# sketchv21111_0.net
KiCad netlist of a schematic drawn in EAGLE
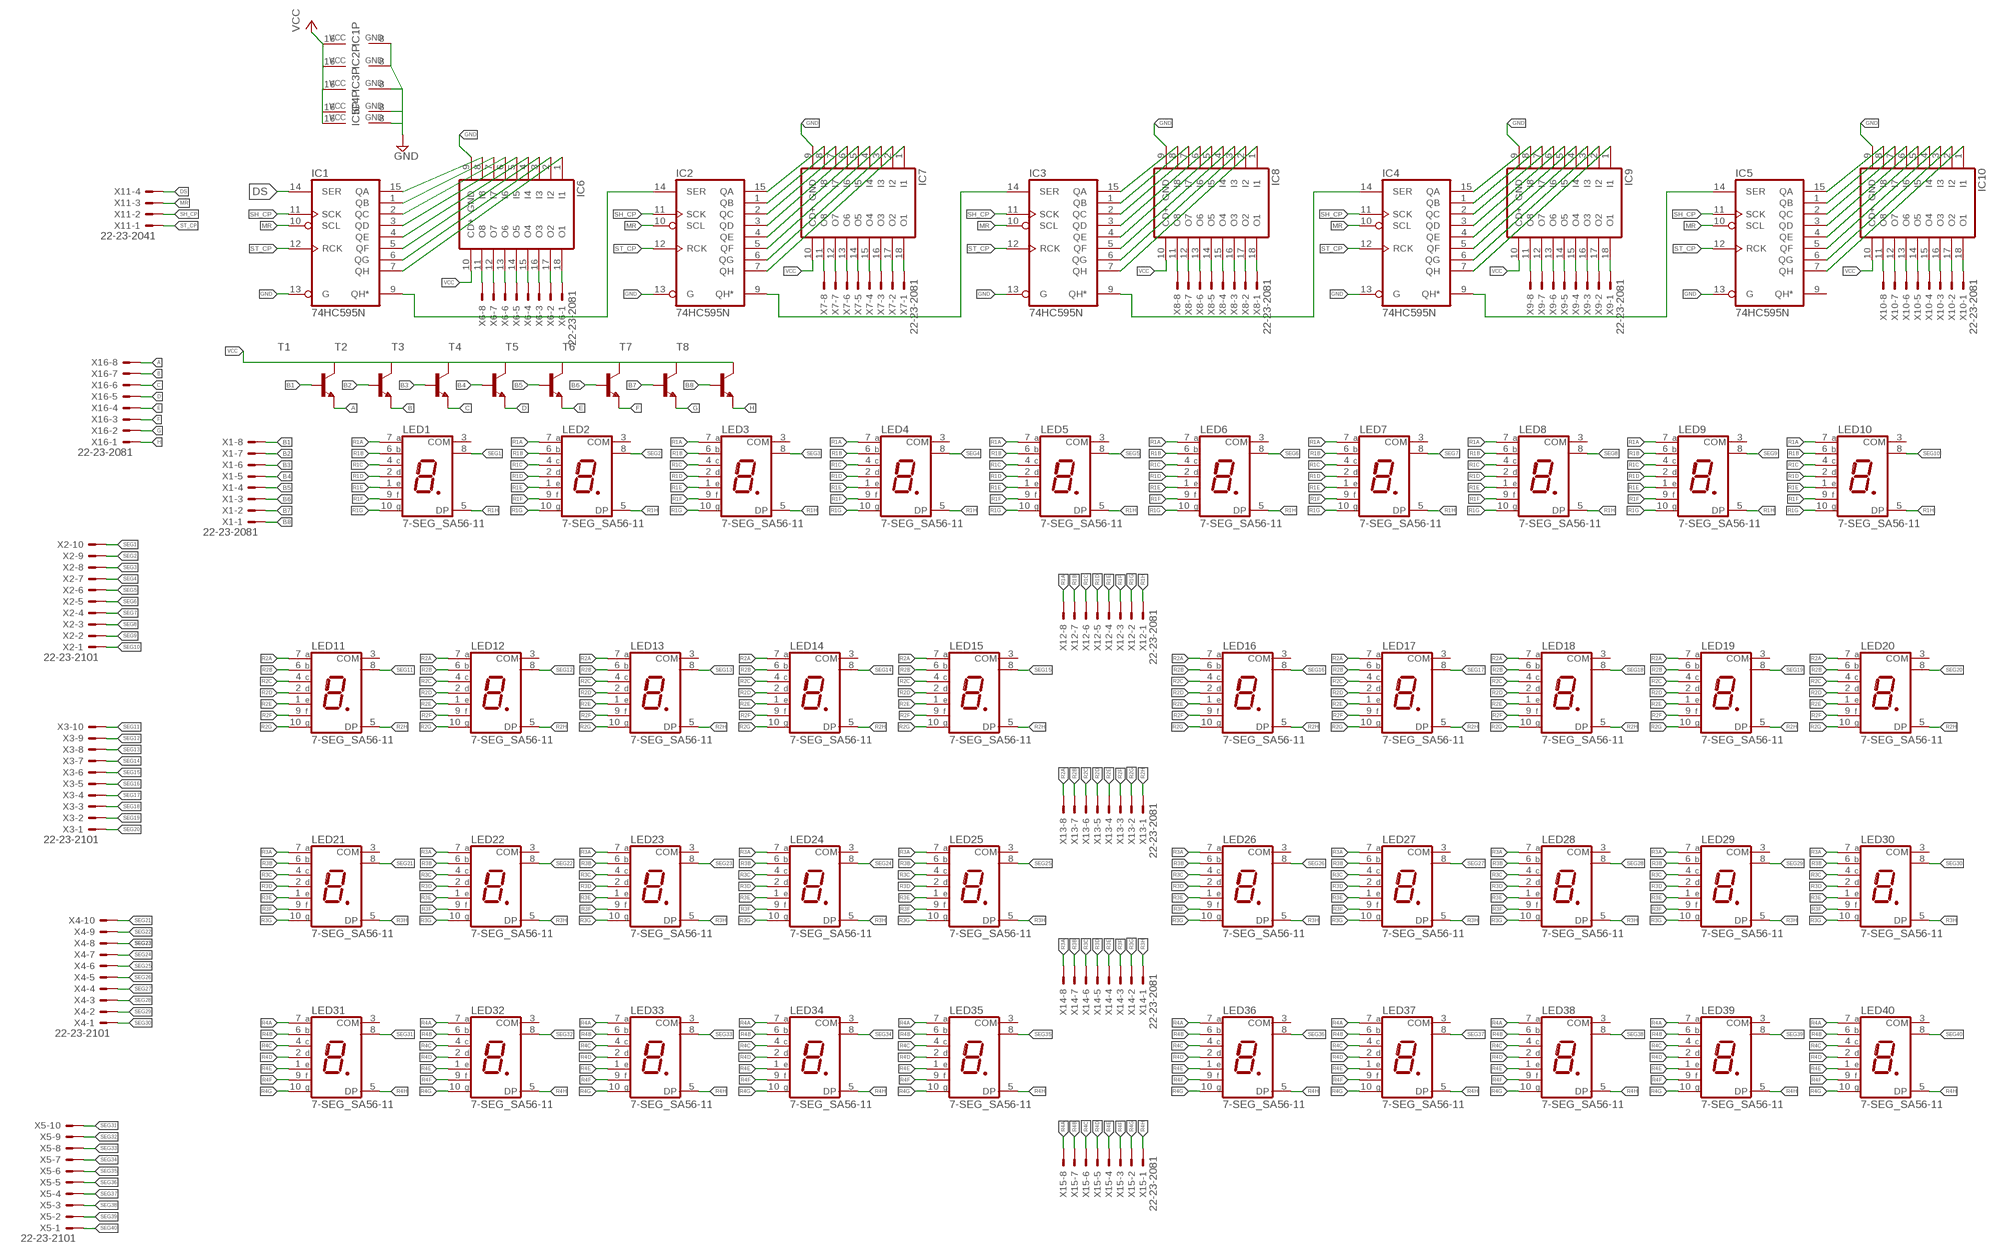
[diagram p0: schematic, sheet 1]

(export (version "E")
  (design (tool "Eeschema 10.0.6"))
  (components
    (comp (ref "IC1")
      (value "74HC595N")
      (footprint "eagle-import:DIL16")
      (libsource (lib "eagle-import") (part "74595NHC"))
    )
    (comp (ref "IC2")
      (value "74HC595N")
      (footprint "eagle-import:DIL16")
      (libsource (lib "eagle-import") (part "74595NHC"))
    )
    (comp (ref "IC3")
      (value "74HC595N")
      (footprint "eagle-import:DIL16")
      (libsource (lib "eagle-import") (part "74595NHC"))
    )
    (comp (ref "IC4")
      (value "74HC595N")
      (footprint "eagle-import:DIL16")
      (libsource (lib "eagle-import") (part "74595NHC"))
    )
    (comp (ref "IC5")
      (value "74HC595N")
      (footprint "eagle-import:DIL16")
      (libsource (lib "eagle-import") (part "74595NHC"))
    )
    (comp (ref "IC6")
      (value "ULN2803A")
      (footprint "eagle-import:DIL18")
      (libsource (lib "eagle-import") (part "ULN2803A"))
    )
    (comp (ref "IC7")
      (value "ULN2803A")
      (footprint "eagle-import:DIL18")
      (libsource (lib "eagle-import") (part "ULN2803A"))
    )
    (comp (ref "IC8")
      (value "ULN2803A")
      (footprint "eagle-import:DIL18")
      (libsource (lib "eagle-import") (part "ULN2803A"))
    )
    (comp (ref "IC9")
      (value "ULN2803A")
      (footprint "eagle-import:DIL18")
      (libsource (lib "eagle-import") (part "ULN2803A"))
    )
    (comp (ref "IC10")
      (value "ULN2803A")
      (footprint "eagle-import:DIL18")
      (libsource (lib "eagle-import") (part "ULN2803A"))
    )
    (comp (ref "LED1")
      (value "7-SEG_SA56-11")
      (footprint "eagle-import:SA56-11")
      (libsource (lib "eagle-import") (part "7-SEG_SA56-11"))
    )
    (comp (ref "LED2")
      (value "7-SEG_SA56-11")
      (footprint "eagle-import:SA56-11")
      (libsource (lib "eagle-import") (part "7-SEG_SA56-11"))
    )
    (comp (ref "LED3")
      (value "7-SEG_SA56-11")
      (footprint "eagle-import:SA56-11")
      (libsource (lib "eagle-import") (part "7-SEG_SA56-11"))
    )
    (comp (ref "LED4")
      (value "7-SEG_SA56-11")
      (footprint "eagle-import:SA56-11")
      (libsource (lib "eagle-import") (part "7-SEG_SA56-11"))
    )
    (comp (ref "LED5")
      (value "7-SEG_SA56-11")
      (footprint "eagle-import:SA56-11")
      (libsource (lib "eagle-import") (part "7-SEG_SA56-11"))
    )
    (comp (ref "LED6")
      (value "7-SEG_SA56-11")
      (footprint "eagle-import:SA56-11")
      (libsource (lib "eagle-import") (part "7-SEG_SA56-11"))
    )
    (comp (ref "LED7")
      (value "7-SEG_SA56-11")
      (footprint "eagle-import:SA56-11")
      (libsource (lib "eagle-import") (part "7-SEG_SA56-11"))
    )
    (comp (ref "LED8")
      (value "7-SEG_SA56-11")
      (footprint "eagle-import:SA56-11")
      (libsource (lib "eagle-import") (part "7-SEG_SA56-11"))
    )
    (comp (ref "LED9")
      (value "7-SEG_SA56-11")
      (footprint "eagle-import:SA56-11")
      (libsource (lib "eagle-import") (part "7-SEG_SA56-11"))
    )
    (comp (ref "LED10")
      (value "7-SEG_SA56-11")
      (footprint "eagle-import:SA56-11")
      (libsource (lib "eagle-import") (part "7-SEG_SA56-11"))
    )
    (comp (ref "LED11")
      (value "7-SEG_SA56-11")
      (footprint "eagle-import:SA56-11")
      (libsource (lib "eagle-import") (part "7-SEG_SA56-11"))
    )
    (comp (ref "LED12")
      (value "7-SEG_SA56-11")
      (footprint "eagle-import:SA56-11")
      (libsource (lib "eagle-import") (part "7-SEG_SA56-11"))
    )
    (comp (ref "LED13")
      (value "7-SEG_SA56-11")
      (footprint "eagle-import:SA56-11")
      (libsource (lib "eagle-import") (part "7-SEG_SA56-11"))
    )
    (comp (ref "LED14")
      (value "7-SEG_SA56-11")
      (footprint "eagle-import:SA56-11")
      (libsource (lib "eagle-import") (part "7-SEG_SA56-11"))
    )
    (comp (ref "LED15")
      (value "7-SEG_SA56-11")
      (footprint "eagle-import:SA56-11")
      (libsource (lib "eagle-import") (part "7-SEG_SA56-11"))
    )
    (comp (ref "LED16")
      (value "7-SEG_SA56-11")
      (footprint "eagle-import:SA56-11")
      (libsource (lib "eagle-import") (part "7-SEG_SA56-11"))
    )
    (comp (ref "LED17")
      (value "7-SEG_SA56-11")
      (footprint "eagle-import:SA56-11")
      (libsource (lib "eagle-import") (part "7-SEG_SA56-11"))
    )
    (comp (ref "LED18")
      (value "7-SEG_SA56-11")
      (footprint "eagle-import:SA56-11")
      (libsource (lib "eagle-import") (part "7-SEG_SA56-11"))
    )
    (comp (ref "LED19")
      (value "7-SEG_SA56-11")
      (footprint "eagle-import:SA56-11")
      (libsource (lib "eagle-import") (part "7-SEG_SA56-11"))
    )
    (comp (ref "LED20")
      (value "7-SEG_SA56-11")
      (footprint "eagle-import:SA56-11")
      (libsource (lib "eagle-import") (part "7-SEG_SA56-11"))
    )
    (comp (ref "LED21")
      (value "7-SEG_SA56-11")
      (footprint "eagle-import:SA56-11")
      (libsource (lib "eagle-import") (part "7-SEG_SA56-11"))
    )
    (comp (ref "LED22")
      (value "7-SEG_SA56-11")
      (footprint "eagle-import:SA56-11")
      (libsource (lib "eagle-import") (part "7-SEG_SA56-11"))
    )
    (comp (ref "LED23")
      (value "7-SEG_SA56-11")
      (footprint "eagle-import:SA56-11")
      (libsource (lib "eagle-import") (part "7-SEG_SA56-11"))
    )
    (comp (ref "LED24")
      (value "7-SEG_SA56-11")
      (footprint "eagle-import:SA56-11")
      (libsource (lib "eagle-import") (part "7-SEG_SA56-11"))
    )
    (comp (ref "LED25")
      (value "7-SEG_SA56-11")
      (footprint "eagle-import:SA56-11")
      (libsource (lib "eagle-import") (part "7-SEG_SA56-11"))
    )
    (comp (ref "LED26")
      (value "7-SEG_SA56-11")
      (footprint "eagle-import:SA56-11")
      (libsource (lib "eagle-import") (part "7-SEG_SA56-11"))
    )
    (comp (ref "LED27")
      (value "7-SEG_SA56-11")
      (footprint "eagle-import:SA56-11")
      (libsource (lib "eagle-import") (part "7-SEG_SA56-11"))
    )
    (comp (ref "LED28")
      (value "7-SEG_SA56-11")
      (footprint "eagle-import:SA56-11")
      (libsource (lib "eagle-import") (part "7-SEG_SA56-11"))
    )
    (comp (ref "LED29")
      (value "7-SEG_SA56-11")
      (footprint "eagle-import:SA56-11")
      (libsource (lib "eagle-import") (part "7-SEG_SA56-11"))
    )
    (comp (ref "LED30")
      (value "7-SEG_SA56-11")
      (footprint "eagle-import:SA56-11")
      (libsource (lib "eagle-import") (part "7-SEG_SA56-11"))
    )
    (comp (ref "LED31")
      (value "7-SEG_SA56-11")
      (footprint "eagle-import:SA56-11")
      (libsource (lib "eagle-import") (part "7-SEG_SA56-11"))
    )
    (comp (ref "LED32")
      (value "7-SEG_SA56-11")
      (footprint "eagle-import:SA56-11")
      (libsource (lib "eagle-import") (part "7-SEG_SA56-11"))
    )
    (comp (ref "LED33")
      (value "7-SEG_SA56-11")
      (footprint "eagle-import:SA56-11")
      (libsource (lib "eagle-import") (part "7-SEG_SA56-11"))
    )
    (comp (ref "LED34")
      (value "7-SEG_SA56-11")
      (footprint "eagle-import:SA56-11")
      (libsource (lib "eagle-import") (part "7-SEG_SA56-11"))
    )
    (comp (ref "LED35")
      (value "7-SEG_SA56-11")
      (footprint "eagle-import:SA56-11")
      (libsource (lib "eagle-import") (part "7-SEG_SA56-11"))
    )
    (comp (ref "LED36")
      (value "7-SEG_SA56-11")
      (footprint "eagle-import:SA56-11")
      (libsource (lib "eagle-import") (part "7-SEG_SA56-11"))
    )
    (comp (ref "LED37")
      (value "7-SEG_SA56-11")
      (footprint "eagle-import:SA56-11")
      (libsource (lib "eagle-import") (part "7-SEG_SA56-11"))
    )
    (comp (ref "LED38")
      (value "7-SEG_SA56-11")
      (footprint "eagle-import:SA56-11")
      (libsource (lib "eagle-import") (part "7-SEG_SA56-11"))
    )
    (comp (ref "LED39")
      (value "7-SEG_SA56-11")
      (footprint "eagle-import:SA56-11")
      (libsource (lib "eagle-import") (part "7-SEG_SA56-11"))
    )
    (comp (ref "LED40")
      (value "7-SEG_SA56-11")
      (footprint "eagle-import:SA56-11")
      (libsource (lib "eagle-import") (part "7-SEG_SA56-11"))
    )
    (comp (ref "T1")
      (value "-NPN-TO92")
      (footprint "eagle-import:TO92")
      (libsource (lib "eagle-import") (part "-NPN-TO92"))
    )
    (comp (ref "T2")
      (value "-NPN-TO92")
      (footprint "eagle-import:TO92")
      (libsource (lib "eagle-import") (part "-NPN-TO92"))
    )
    (comp (ref "T3")
      (value "-NPN-TO92")
      (footprint "eagle-import:TO92")
      (libsource (lib "eagle-import") (part "-NPN-TO92"))
    )
    (comp (ref "T4")
      (value "-NPN-TO92")
      (footprint "eagle-import:TO92")
      (libsource (lib "eagle-import") (part "-NPN-TO92"))
    )
    (comp (ref "T5")
      (value "-NPN-TO92")
      (footprint "eagle-import:TO92")
      (libsource (lib "eagle-import") (part "-NPN-TO92"))
    )
    (comp (ref "T6")
      (value "-NPN-TO92")
      (footprint "eagle-import:TO92")
      (libsource (lib "eagle-import") (part "-NPN-TO92"))
    )
    (comp (ref "T7")
      (value "-NPN-TO92")
      (footprint "eagle-import:TO92")
      (libsource (lib "eagle-import") (part "-NPN-TO92"))
    )
    (comp (ref "T8")
      (value "-NPN-TO92")
      (footprint "eagle-import:TO92")
      (libsource (lib "eagle-import") (part "-NPN-TO92"))
    )
    (comp (ref "X1")
      (value "22-23-2081")
      (footprint "eagle-import:22-23-2081")
      (fields (field (name "MF") "MOLEX"))
      (libsource (lib "eagle-import") (part "22-23-2081"))
    )
    (comp (ref "X2")
      (value "22-23-2101")
      (footprint "eagle-import:22-23-2101")
      (fields (field (name "MF") "MOLEX"))
      (libsource (lib "eagle-import") (part "22-23-2101"))
    )
    (comp (ref "X3")
      (value "22-23-2101")
      (footprint "eagle-import:22-23-2101")
      (fields (field (name "MF") "MOLEX"))
      (libsource (lib "eagle-import") (part "22-23-2101"))
    )
    (comp (ref "X4")
      (value "22-23-2101")
      (footprint "eagle-import:22-23-2101")
      (fields (field (name "MF") "MOLEX"))
      (libsource (lib "eagle-import") (part "22-23-2101"))
    )
    (comp (ref "X5")
      (value "22-23-2101")
      (footprint "eagle-import:22-23-2101")
      (fields (field (name "MF") "MOLEX"))
      (libsource (lib "eagle-import") (part "22-23-2101"))
    )
    (comp (ref "X6")
      (value "22-23-2081")
      (footprint "eagle-import:22-23-2081")
      (fields (field (name "MF") "MOLEX"))
      (libsource (lib "eagle-import") (part "22-23-2081"))
    )
    (comp (ref "X7")
      (value "22-23-2081")
      (footprint "eagle-import:22-23-2081")
      (fields (field (name "MF") "MOLEX"))
      (libsource (lib "eagle-import") (part "22-23-2081"))
    )
    (comp (ref "X8")
      (value "22-23-2081")
      (footprint "eagle-import:22-23-2081")
      (fields (field (name "MF") "MOLEX"))
      (libsource (lib "eagle-import") (part "22-23-2081"))
    )
    (comp (ref "X9")
      (value "22-23-2081")
      (footprint "eagle-import:22-23-2081")
      (fields (field (name "MF") "MOLEX"))
      (libsource (lib "eagle-import") (part "22-23-2081"))
    )
    (comp (ref "X10")
      (value "22-23-2081")
      (footprint "eagle-import:22-23-2081")
      (fields (field (name "MF") "MOLEX"))
      (libsource (lib "eagle-import") (part "22-23-2081"))
    )
    (comp (ref "X11")
      (value "22-23-2041")
      (footprint "eagle-import:22-23-2041")
      (fields (field (name "MF") "MOLEX"))
      (libsource (lib "eagle-import") (part "22-23-2041"))
    )
    (comp (ref "X12")
      (value "22-23-2081")
      (footprint "eagle-import:22-23-2081")
      (fields (field (name "MF") "MOLEX"))
      (libsource (lib "eagle-import") (part "22-23-2081"))
    )
    (comp (ref "X13")
      (value "22-23-2081")
      (footprint "eagle-import:22-23-2081")
      (fields (field (name "MF") "MOLEX"))
      (libsource (lib "eagle-import") (part "22-23-2081"))
    )
    (comp (ref "X14")
      (value "22-23-2081")
      (footprint "eagle-import:22-23-2081")
      (fields (field (name "MF") "MOLEX"))
      (libsource (lib "eagle-import") (part "22-23-2081"))
    )
    (comp (ref "X15")
      (value "22-23-2081")
      (footprint "eagle-import:22-23-2081")
      (fields (field (name "MF") "MOLEX"))
      (libsource (lib "eagle-import") (part "22-23-2081"))
    )
    (comp (ref "X16")
      (value "22-23-2081")
      (footprint "eagle-import:22-23-2081")
      (fields (field (name "MF") "MOLEX"))
      (libsource (lib "eagle-import") (part "22-23-2081"))
    )
  )
  (nets
    (net (code "1") (name "A") (class "Default")
      (node (ref "T1") (pin "1") (pinfunction "E_1") (pintype "passive"))
      (node (ref "X16") (pin "8") (pinfunction "S_8") (pintype "passive"))
    )
    (net (code "2") (name "B") (class "Default")
      (node (ref "T2") (pin "1") (pinfunction "E_1") (pintype "passive"))
      (node (ref "X16") (pin "7") (pinfunction "S_7") (pintype "passive"))
    )
    (net (code "3") (name "B1") (class "Default")
      (node (ref "T1") (pin "2") (pinfunction "B_2") (pintype "passive"))
      (node (ref "X1") (pin "8") (pinfunction "S_8") (pintype "passive"))
    )
    (net (code "4") (name "B2") (class "Default")
      (node (ref "T2") (pin "2") (pinfunction "B_2") (pintype "passive"))
      (node (ref "X1") (pin "7") (pinfunction "S_7") (pintype "passive"))
    )
    (net (code "5") (name "B3") (class "Default")
      (node (ref "T3") (pin "2") (pinfunction "B_2") (pintype "passive"))
      (node (ref "X1") (pin "6") (pinfunction "S_6") (pintype "passive"))
    )
    (net (code "6") (name "B4") (class "Default")
      (node (ref "T4") (pin "2") (pinfunction "B_2") (pintype "passive"))
      (node (ref "X1") (pin "5") (pinfunction "S_5") (pintype "passive"))
    )
    (net (code "7") (name "B5") (class "Default")
      (node (ref "T5") (pin "2") (pinfunction "B_2") (pintype "passive"))
      (node (ref "X1") (pin "4") (pinfunction "S_4") (pintype "passive"))
    )
    (net (code "8") (name "B6") (class "Default")
      (node (ref "T6") (pin "2") (pinfunction "B_2") (pintype "passive"))
      (node (ref "X1") (pin "3") (pinfunction "S_3") (pintype "passive"))
    )
    (net (code "9") (name "B7") (class "Default")
      (node (ref "T7") (pin "2") (pinfunction "B_2") (pintype "passive"))
      (node (ref "X1") (pin "2") (pinfunction "S_2") (pintype "passive"))
    )
    (net (code "10") (name "B8") (class "Default")
      (node (ref "T8") (pin "2") (pinfunction "B_2") (pintype "passive"))
      (node (ref "X1") (pin "1") (pinfunction "S_1") (pintype "passive"))
    )
    (net (code "11") (name "C") (class "Default")
      (node (ref "T3") (pin "1") (pinfunction "E_1") (pintype "passive"))
      (node (ref "X16") (pin "6") (pinfunction "S_6") (pintype "passive"))
    )
    (net (code "12") (name "D") (class "Default")
      (node (ref "T4") (pin "1") (pinfunction "E_1") (pintype "passive"))
      (node (ref "X16") (pin "5") (pinfunction "S_5") (pintype "passive"))
    )
    (net (code "13") (name "DS") (class "Default")
      (node (ref "IC1") (pin "14") (pinfunction "SER_14") (pintype "input"))
      (node (ref "X11") (pin "4") (pinfunction "S_4") (pintype "passive"))
    )
    (net (code "14") (name "E") (class "Default")
      (node (ref "T5") (pin "1") (pinfunction "E_1") (pintype "passive"))
      (node (ref "X16") (pin "4") (pinfunction "S_4") (pintype "passive"))
    )
    (net (code "15") (name "F") (class "Default")
      (node (ref "T6") (pin "1") (pinfunction "E_1") (pintype "passive"))
      (node (ref "X16") (pin "3") (pinfunction "S_3") (pintype "passive"))
    )
    (net (code "16") (name "G") (class "Default")
      (node (ref "T7") (pin "1") (pinfunction "E_1") (pintype "passive"))
      (node (ref "X16") (pin "2") (pinfunction "S_2") (pintype "passive"))
    )
    (net (code "17") (name "GND") (class "Default")
      (node (ref "IC1") (pin "13") (pinfunction "G_13") (pintype "input"))
      (node (ref "IC1") (pin "8") (pinfunction "GND_8") (pintype "power_in"))
      (node (ref "IC10") (pin "9") (pinfunction "GND_9") (pintype "power_in"))
      (node (ref "IC2") (pin "13") (pinfunction "G_13") (pintype "input"))
      (node (ref "IC2") (pin "8") (pinfunction "GND_8") (pintype "power_in"))
      (node (ref "IC3") (pin "13") (pinfunction "G_13") (pintype "input"))
      (node (ref "IC3") (pin "8") (pinfunction "GND_8") (pintype "power_in"))
      (node (ref "IC4") (pin "13") (pinfunction "G_13") (pintype "input"))
      (node (ref "IC4") (pin "8") (pinfunction "GND_8") (pintype "power_in"))
      (node (ref "IC5") (pin "13") (pinfunction "G_13") (pintype "input"))
      (node (ref "IC5") (pin "8") (pinfunction "GND_8") (pintype "power_in"))
      (node (ref "IC6") (pin "9") (pinfunction "GND_9") (pintype "power_in"))
      (node (ref "IC7") (pin "9") (pinfunction "GND_9") (pintype "power_in"))
      (node (ref "IC8") (pin "9") (pinfunction "GND_9") (pintype "power_in"))
      (node (ref "IC9") (pin "9") (pinfunction "GND_9") (pintype "power_in"))
    )
    (net (code "18") (name "H") (class "Default")
      (node (ref "T8") (pin "1") (pinfunction "E_1") (pintype "passive"))
      (node (ref "X16") (pin "1") (pinfunction "S_1") (pintype "passive"))
    )
    (net (code "19") (name "MR") (class "Default")
      (node (ref "IC1") (pin "10") (pinfunction "SCL_10") (pintype "input"))
      (node (ref "IC2") (pin "10") (pinfunction "SCL_10") (pintype "input"))
      (node (ref "IC3") (pin "10") (pinfunction "SCL_10") (pintype "input"))
      (node (ref "IC4") (pin "10") (pinfunction "SCL_10") (pintype "input"))
      (node (ref "IC5") (pin "10") (pinfunction "SCL_10") (pintype "input"))
      (node (ref "X11") (pin "3") (pinfunction "S_3") (pintype "passive"))
    )
    (net (code "20") (name "Net-(IC1A-QA)") (class "Default")
      (node (ref "IC1") (pin "15") (pinfunction "QA_15") (pintype "tri_state"))
      (node (ref "IC6") (pin "8") (pinfunction "I8_8") (pintype "input"))
    )
    (net (code "21") (name "Net-(IC1A-QB)") (class "Default")
      (node (ref "IC1") (pin "1") (pinfunction "QB_1") (pintype "tri_state"))
      (node (ref "IC6") (pin "7") (pinfunction "I7_7") (pintype "input"))
    )
    (net (code "22") (name "Net-(IC1A-QC)") (class "Default")
      (node (ref "IC1") (pin "2") (pinfunction "QC_2") (pintype "tri_state"))
      (node (ref "IC6") (pin "6") (pinfunction "I6_6") (pintype "input"))
    )
    (net (code "23") (name "Net-(IC1A-QD)") (class "Default")
      (node (ref "IC1") (pin "3") (pinfunction "QD_3") (pintype "tri_state"))
      (node (ref "IC6") (pin "5") (pinfunction "I5_5") (pintype "input"))
    )
    (net (code "24") (name "Net-(IC1A-QE)") (class "Default")
      (node (ref "IC1") (pin "4") (pinfunction "QE_4") (pintype "tri_state"))
      (node (ref "IC6") (pin "4") (pinfunction "I4_4") (pintype "input"))
    )
    (net (code "25") (name "Net-(IC1A-QF)") (class "Default")
      (node (ref "IC1") (pin "5") (pinfunction "QF_5") (pintype "tri_state"))
      (node (ref "IC6") (pin "3") (pinfunction "I3_3") (pintype "input"))
    )
    (net (code "26") (name "Net-(IC1A-QG)") (class "Default")
      (node (ref "IC1") (pin "6") (pinfunction "QG_6") (pintype "tri_state"))
      (node (ref "IC6") (pin "2") (pinfunction "I2_2") (pintype "input"))
    )
    (net (code "27") (name "Net-(IC1A-QH)") (class "Default")
      (node (ref "IC1") (pin "7") (pinfunction "QH_7") (pintype "tri_state"))
      (node (ref "IC6") (pin "1") (pinfunction "I1_1") (pintype "input"))
    )
    (net (code "28") (name "Net-(IC1A-QH*)") (class "Default")
      (node (ref "IC1") (pin "9") (pinfunction "QH*_9") (pintype "tri_state"))
      (node (ref "IC2") (pin "14") (pinfunction "SER_14") (pintype "input"))
    )
    (net (code "29") (name "Net-(IC2A-QA)") (class "Default")
      (node (ref "IC2") (pin "15") (pinfunction "QA_15") (pintype "tri_state"))
      (node (ref "IC7") (pin "8") (pinfunction "I8_8") (pintype "input"))
    )
    (net (code "30") (name "Net-(IC2A-QB)") (class "Default")
      (node (ref "IC2") (pin "1") (pinfunction "QB_1") (pintype "tri_state"))
      (node (ref "IC7") (pin "7") (pinfunction "I7_7") (pintype "input"))
    )
    (net (code "31") (name "Net-(IC2A-QC)") (class "Default")
      (node (ref "IC2") (pin "2") (pinfunction "QC_2") (pintype "tri_state"))
      (node (ref "IC7") (pin "6") (pinfunction "I6_6") (pintype "input"))
    )
    (net (code "32") (name "Net-(IC2A-QD)") (class "Default")
      (node (ref "IC2") (pin "3") (pinfunction "QD_3") (pintype "tri_state"))
      (node (ref "IC7") (pin "5") (pinfunction "I5_5") (pintype "input"))
    )
    (net (code "33") (name "Net-(IC2A-QE)") (class "Default")
      (node (ref "IC2") (pin "4") (pinfunction "QE_4") (pintype "tri_state"))
      (node (ref "IC7") (pin "4") (pinfunction "I4_4") (pintype "input"))
    )
    (net (code "34") (name "Net-(IC2A-QF)") (class "Default")
      (node (ref "IC2") (pin "5") (pinfunction "QF_5") (pintype "tri_state"))
      (node (ref "IC7") (pin "3") (pinfunction "I3_3") (pintype "input"))
    )
    (net (code "35") (name "Net-(IC2A-QG)") (class "Default")
      (node (ref "IC2") (pin "6") (pinfunction "QG_6") (pintype "tri_state"))
      (node (ref "IC7") (pin "2") (pinfunction "I2_2") (pintype "input"))
    )
    (net (code "36") (name "Net-(IC2A-QH)") (class "Default")
      (node (ref "IC2") (pin "7") (pinfunction "QH_7") (pintype "tri_state"))
      (node (ref "IC7") (pin "1") (pinfunction "I1_1") (pintype "input"))
    )
    (net (code "37") (name "Net-(IC2A-QH*)") (class "Default")
      (node (ref "IC2") (pin "9") (pinfunction "QH*_9") (pintype "tri_state"))
      (node (ref "IC3") (pin "14") (pinfunction "SER_14") (pintype "input"))
    )
    (net (code "38") (name "Net-(IC3A-QA)") (class "Default")
      (node (ref "IC3") (pin "15") (pinfunction "QA_15") (pintype "tri_state"))
      (node (ref "IC8") (pin "8") (pinfunction "I8_8") (pintype "input"))
    )
    (net (code "39") (name "Net-(IC3A-QB)") (class "Default")
      (node (ref "IC3") (pin "1") (pinfunction "QB_1") (pintype "tri_state"))
      (node (ref "IC8") (pin "7") (pinfunction "I7_7") (pintype "input"))
    )
    (net (code "40") (name "Net-(IC3A-QC)") (class "Default")
      (node (ref "IC3") (pin "2") (pinfunction "QC_2") (pintype "tri_state"))
      (node (ref "IC8") (pin "6") (pinfunction "I6_6") (pintype "input"))
    )
    (net (code "41") (name "Net-(IC3A-QD)") (class "Default")
      (node (ref "IC3") (pin "3") (pinfunction "QD_3") (pintype "tri_state"))
      (node (ref "IC8") (pin "5") (pinfunction "I5_5") (pintype "input"))
    )
    (net (code "42") (name "Net-(IC3A-QE)") (class "Default")
      (node (ref "IC3") (pin "4") (pinfunction "QE_4") (pintype "tri_state"))
      (node (ref "IC8") (pin "4") (pinfunction "I4_4") (pintype "input"))
    )
    (net (code "43") (name "Net-(IC3A-QF)") (class "Default")
      (node (ref "IC3") (pin "5") (pinfunction "QF_5") (pintype "tri_state"))
      (node (ref "IC8") (pin "3") (pinfunction "I3_3") (pintype "input"))
    )
    (net (code "44") (name "Net-(IC3A-QG)") (class "Default")
      (node (ref "IC3") (pin "6") (pinfunction "QG_6") (pintype "tri_state"))
      (node (ref "IC8") (pin "2") (pinfunction "I2_2") (pintype "input"))
    )
    (net (code "45") (name "Net-(IC3A-QH)") (class "Default")
      (node (ref "IC3") (pin "7") (pinfunction "QH_7") (pintype "tri_state"))
      (node (ref "IC8") (pin "1") (pinfunction "I1_1") (pintype "input"))
    )
    (net (code "46") (name "Net-(IC3A-QH*)") (class "Default")
      (node (ref "IC3") (pin "9") (pinfunction "QH*_9") (pintype "tri_state"))
      (node (ref "IC4") (pin "14") (pinfunction "SER_14") (pintype "input"))
    )
    (net (code "47") (name "Net-(IC4A-QA)") (class "Default")
      (node (ref "IC4") (pin "15") (pinfunction "QA_15") (pintype "tri_state"))
      (node (ref "IC9") (pin "8") (pinfunction "I8_8") (pintype "input"))
    )
    (net (code "48") (name "Net-(IC4A-QB)") (class "Default")
      (node (ref "IC4") (pin "1") (pinfunction "QB_1") (pintype "tri_state"))
      (node (ref "IC9") (pin "7") (pinfunction "I7_7") (pintype "input"))
    )
    (net (code "49") (name "Net-(IC4A-QC)") (class "Default")
      (node (ref "IC4") (pin "2") (pinfunction "QC_2") (pintype "tri_state"))
      (node (ref "IC9") (pin "6") (pinfunction "I6_6") (pintype "input"))
    )
    (net (code "50") (name "Net-(IC4A-QD)") (class "Default")
      (node (ref "IC4") (pin "3") (pinfunction "QD_3") (pintype "tri_state"))
      (node (ref "IC9") (pin "5") (pinfunction "I5_5") (pintype "input"))
    )
    (net (code "51") (name "Net-(IC4A-QE)") (class "Default")
      (node (ref "IC4") (pin "4") (pinfunction "QE_4") (pintype "tri_state"))
      (node (ref "IC9") (pin "4") (pinfunction "I4_4") (pintype "input"))
    )
    (net (code "52") (name "Net-(IC4A-QF)") (class "Default")
      (node (ref "IC4") (pin "5") (pinfunction "QF_5") (pintype "tri_state"))
      (node (ref "IC9") (pin "3") (pinfunction "I3_3") (pintype "input"))
    )
    (net (code "53") (name "Net-(IC4A-QG)") (class "Default")
      (node (ref "IC4") (pin "6") (pinfunction "QG_6") (pintype "tri_state"))
      (node (ref "IC9") (pin "2") (pinfunction "I2_2") (pintype "input"))
    )
    (net (code "54") (name "Net-(IC4A-QH)") (class "Default")
      (node (ref "IC4") (pin "7") (pinfunction "QH_7") (pintype "tri_state"))
      (node (ref "IC9") (pin "1") (pinfunction "I1_1") (pintype "input"))
    )
    (net (code "55") (name "Net-(IC4A-QH*)") (class "Default")
      (node (ref "IC4") (pin "9") (pinfunction "QH*_9") (pintype "tri_state"))
      (node (ref "IC5") (pin "14") (pinfunction "SER_14") (pintype "input"))
    )
    (net (code "56") (name "Net-(IC6-O1)") (class "Default")
      (node (ref "IC6") (pin "18") (pinfunction "O1_18") (pintype "open_collector"))
      (node (ref "X6") (pin "1") (pinfunction "S_1") (pintype "passive"))
    )
    (net (code "57") (name "Net-(IC6-O2)") (class "Default")
      (node (ref "IC6") (pin "17") (pinfunction "O2_17") (pintype "open_collector"))
      (node (ref "X6") (pin "2") (pinfunction "S_2") (pintype "passive"))
    )
    (net (code "58") (name "Net-(IC6-O3)") (class "Default")
      (node (ref "IC6") (pin "16") (pinfunction "O3_16") (pintype "open_collector"))
      (node (ref "X6") (pin "3") (pinfunction "S_3") (pintype "passive"))
    )
    (net (code "59") (name "Net-(IC6-O4)") (class "Default")
      (node (ref "IC6") (pin "15") (pinfunction "O4_15") (pintype "open_collector"))
      (node (ref "X6") (pin "4") (pinfunction "S_4") (pintype "passive"))
    )
    (net (code "60") (name "Net-(IC6-O5)") (class "Default")
      (node (ref "IC6") (pin "14") (pinfunction "O5_14") (pintype "open_collector"))
      (node (ref "X6") (pin "5") (pinfunction "S_5") (pintype "passive"))
    )
    (net (code "61") (name "Net-(IC6-O6)") (class "Default")
      (node (ref "IC6") (pin "13") (pinfunction "O6_13") (pintype "open_collector"))
      (node (ref "X6") (pin "6") (pinfunction "S_6") (pintype "passive"))
    )
    (net (code "62") (name "Net-(IC6-O7)") (class "Default")
      (node (ref "IC6") (pin "12") (pinfunction "O7_12") (pintype "open_collector"))
      (node (ref "X6") (pin "7") (pinfunction "S_7") (pintype "passive"))
    )
    (net (code "63") (name "Net-(IC6-O8)") (class "Default")
      (node (ref "IC6") (pin "11") (pinfunction "O8_11") (pintype "open_collector"))
      (node (ref "X6") (pin "8") (pinfunction "S_8") (pintype "passive"))
    )
    (net (code "64") (name "Net-(IC7-O1)") (class "Default")
      (node (ref "IC7") (pin "18") (pinfunction "O1_18") (pintype "open_collector"))
      (node (ref "X7") (pin "1") (pinfunction "S_1") (pintype "passive"))
    )
    (net (code "65") (name "Net-(IC7-O2)") (class "Default")
      (node (ref "IC7") (pin "17") (pinfunction "O2_17") (pintype "open_collector"))
      (node (ref "X7") (pin "2") (pinfunction "S_2") (pintype "passive"))
    )
    (net (code "66") (name "Net-(IC7-O3)") (class "Default")
      (node (ref "IC7") (pin "16") (pinfunction "O3_16") (pintype "open_collector"))
      (node (ref "X7") (pin "3") (pinfunction "S_3") (pintype "passive"))
    )
    (net (code "67") (name "Net-(IC7-O4)") (class "Default")
      (node (ref "IC7") (pin "15") (pinfunction "O4_15") (pintype "open_collector"))
      (node (ref "X7") (pin "4") (pinfunction "S_4") (pintype "passive"))
    )
    (net (code "68") (name "Net-(IC7-O5)") (class "Default")
      (node (ref "IC7") (pin "14") (pinfunction "O5_14") (pintype "open_collector"))
      (node (ref "X7") (pin "5") (pinfunction "S_5") (pintype "passive"))
    )
    (net (code "69") (name "Net-(IC7-O6)") (class "Default")
      (node (ref "IC7") (pin "13") (pinfunction "O6_13") (pintype "open_collector"))
      (node (ref "X7") (pin "6") (pinfunction "S_6") (pintype "passive"))
    )
    (net (code "70") (name "Net-(IC7-O7)") (class "Default")
      (node (ref "IC7") (pin "12") (pinfunction "O7_12") (pintype "open_collector"))
      (node (ref "X7") (pin "7") (pinfunction "S_7") (pintype "passive"))
    )
    (net (code "71") (name "Net-(IC7-O8)") (class "Default")
      (node (ref "IC7") (pin "11") (pinfunction "O8_11") (pintype "open_collector"))
      (node (ref "X7") (pin "8") (pinfunction "S_8") (pintype "passive"))
    )
    (net (code "72") (name "Net-(IC8-O1)") (class "Default")
      (node (ref "IC8") (pin "18") (pinfunction "O1_18") (pintype "open_collector"))
      (node (ref "X8") (pin "1") (pinfunction "S_1") (pintype "passive"))
    )
    (net (code "73") (name "Net-(IC8-O2)") (class "Default")
      (node (ref "IC8") (pin "17") (pinfunction "O2_17") (pintype "open_collector"))
      (node (ref "X8") (pin "2") (pinfunction "S_2") (pintype "passive"))
    )
    (net (code "74") (name "Net-(IC8-O3)") (class "Default")
      (node (ref "IC8") (pin "16") (pinfunction "O3_16") (pintype "open_collector"))
      (node (ref "X8") (pin "3") (pinfunction "S_3") (pintype "passive"))
    )
    (net (code "75") (name "Net-(IC8-O4)") (class "Default")
      (node (ref "IC8") (pin "15") (pinfunction "O4_15") (pintype "open_collector"))
      (node (ref "X8") (pin "4") (pinfunction "S_4") (pintype "passive"))
    )
    (net (code "76") (name "Net-(IC8-O5)") (class "Default")
      (node (ref "IC8") (pin "14") (pinfunction "O5_14") (pintype "open_collector"))
      (node (ref "X8") (pin "5") (pinfunction "S_5") (pintype "passive"))
    )
    (net (code "77") (name "Net-(IC8-O6)") (class "Default")
      (node (ref "IC8") (pin "13") (pinfunction "O6_13") (pintype "open_collector"))
      (node (ref "X8") (pin "6") (pinfunction "S_6") (pintype "passive"))
    )
    (net (code "78") (name "Net-(IC8-O7)") (class "Default")
      (node (ref "IC8") (pin "12") (pinfunction "O7_12") (pintype "open_collector"))
      (node (ref "X8") (pin "7") (pinfunction "S_7") (pintype "passive"))
    )
    (net (code "79") (name "Net-(IC8-O8)") (class "Default")
      (node (ref "IC8") (pin "11") (pinfunction "O8_11") (pintype "open_collector"))
      (node (ref "X8") (pin "8") (pinfunction "S_8") (pintype "passive"))
    )
    (net (code "80") (name "Net-(IC9-O1)") (class "Default")
      (node (ref "IC9") (pin "18") (pinfunction "O1_18") (pintype "open_collector"))
      (node (ref "X9") (pin "1") (pinfunction "S_1") (pintype "passive"))
    )
    (net (code "81") (name "Net-(IC9-O2)") (class "Default")
      (node (ref "IC9") (pin "17") (pinfunction "O2_17") (pintype "open_collector"))
      (node (ref "X9") (pin "2") (pinfunction "S_2") (pintype "passive"))
    )
    (net (code "82") (name "Net-(IC9-O3)") (class "Default")
      (node (ref "IC9") (pin "16") (pinfunction "O3_16") (pintype "open_collector"))
      (node (ref "X9") (pin "3") (pinfunction "S_3") (pintype "passive"))
    )
    (net (code "83") (name "Net-(IC9-O4)") (class "Default")
      (node (ref "IC9") (pin "15") (pinfunction "O4_15") (pintype "open_collector"))
      (node (ref "X9") (pin "4") (pinfunction "S_4") (pintype "passive"))
    )
    (net (code "84") (name "Net-(IC9-O5)") (class "Default")
      (node (ref "IC9") (pin "14") (pinfunction "O5_14") (pintype "open_collector"))
      (node (ref "X9") (pin "5") (pinfunction "S_5") (pintype "passive"))
    )
    (net (code "85") (name "Net-(IC9-O6)") (class "Default")
      (node (ref "IC9") (pin "13") (pinfunction "O6_13") (pintype "open_collector"))
      (node (ref "X9") (pin "6") (pinfunction "S_6") (pintype "passive"))
    )
    (net (code "86") (name "Net-(IC9-O7)") (class "Default")
      (node (ref "IC9") (pin "12") (pinfunction "O7_12") (pintype "open_collector"))
      (node (ref "X9") (pin "7") (pinfunction "S_7") (pintype "passive"))
    )
    (net (code "87") (name "Net-(IC9-O8)") (class "Default")
      (node (ref "IC9") (pin "11") (pinfunction "O8_11") (pintype "open_collector"))
      (node (ref "X9") (pin "8") (pinfunction "S_8") (pintype "passive"))
    )
    (net (code "88") (name "Net-(IC10-I1)") (class "Default")
      (node (ref "IC10") (pin "1") (pinfunction "I1_1") (pintype "input"))
      (node (ref "IC5") (pin "7") (pinfunction "QH_7") (pintype "tri_state"))
    )
    (net (code "89") (name "Net-(IC10-I2)") (class "Default")
      (node (ref "IC10") (pin "2") (pinfunction "I2_2") (pintype "input"))
      (node (ref "IC5") (pin "6") (pinfunction "QG_6") (pintype "tri_state"))
    )
    (net (code "90") (name "Net-(IC10-I3)") (class "Default")
      (node (ref "IC10") (pin "3") (pinfunction "I3_3") (pintype "input"))
      (node (ref "IC5") (pin "5") (pinfunction "QF_5") (pintype "tri_state"))
    )
    (net (code "91") (name "Net-(IC10-I4)") (class "Default")
      (node (ref "IC10") (pin "4") (pinfunction "I4_4") (pintype "input"))
      (node (ref "IC5") (pin "4") (pinfunction "QE_4") (pintype "tri_state"))
    )
    (net (code "92") (name "Net-(IC10-I5)") (class "Default")
      (node (ref "IC10") (pin "5") (pinfunction "I5_5") (pintype "input"))
      (node (ref "IC5") (pin "3") (pinfunction "QD_3") (pintype "tri_state"))
    )
    (net (code "93") (name "Net-(IC10-I6)") (class "Default")
      (node (ref "IC10") (pin "6") (pinfunction "I6_6") (pintype "input"))
      (node (ref "IC5") (pin "2") (pinfunction "QC_2") (pintype "tri_state"))
    )
    (net (code "94") (name "Net-(IC10-I7)") (class "Default")
      (node (ref "IC10") (pin "7") (pinfunction "I7_7") (pintype "input"))
      (node (ref "IC5") (pin "1") (pinfunction "QB_1") (pintype "tri_state"))
    )
    (net (code "95") (name "Net-(IC10-I8)") (class "Default")
      (node (ref "IC10") (pin "8") (pinfunction "I8_8") (pintype "input"))
      (node (ref "IC5") (pin "15") (pinfunction "QA_15") (pintype "tri_state"))
    )
    (net (code "96") (name "Net-(IC10-O1)") (class "Default")
      (node (ref "IC10") (pin "18") (pinfunction "O1_18") (pintype "open_collector"))
      (node (ref "X10") (pin "1") (pinfunction "S_1") (pintype "passive"))
    )
    (net (code "97") (name "Net-(IC10-O2)") (class "Default")
      (node (ref "IC10") (pin "17") (pinfunction "O2_17") (pintype "open_collector"))
      (node (ref "X10") (pin "2") (pinfunction "S_2") (pintype "passive"))
    )
    (net (code "98") (name "Net-(IC10-O3)") (class "Default")
      (node (ref "IC10") (pin "16") (pinfunction "O3_16") (pintype "open_collector"))
      (node (ref "X10") (pin "3") (pinfunction "S_3") (pintype "passive"))
    )
    (net (code "99") (name "Net-(IC10-O4)") (class "Default")
      (node (ref "IC10") (pin "15") (pinfunction "O4_15") (pintype "open_collector"))
      (node (ref "X10") (pin "4") (pinfunction "S_4") (pintype "passive"))
    )
    (net (code "100") (name "Net-(IC10-O5)") (class "Default")
      (node (ref "IC10") (pin "14") (pinfunction "O5_14") (pintype "open_collector"))
      (node (ref "X10") (pin "5") (pinfunction "S_5") (pintype "passive"))
    )
    (net (code "101") (name "Net-(IC10-O6)") (class "Default")
      (node (ref "IC10") (pin "13") (pinfunction "O6_13") (pintype "open_collector"))
      (node (ref "X10") (pin "6") (pinfunction "S_6") (pintype "passive"))
    )
    (net (code "102") (name "Net-(IC10-O7)") (class "Default")
      (node (ref "IC10") (pin "12") (pinfunction "O7_12") (pintype "open_collector"))
      (node (ref "X10") (pin "7") (pinfunction "S_7") (pintype "passive"))
    )
    (net (code "103") (name "Net-(IC10-O8)") (class "Default")
      (node (ref "IC10") (pin "11") (pinfunction "O8_11") (pintype "open_collector"))
      (node (ref "X10") (pin "8") (pinfunction "S_8") (pintype "passive"))
    )
    (net (code "104") (name "R1A") (class "Default")
      (node (ref "LED1") (pin "7") (pinfunction "A_7") (pintype "passive"))
      (node (ref "LED10") (pin "7") (pinfunction "A_7") (pintype "passive"))
      (node (ref "LED2") (pin "7") (pinfunction "A_7") (pintype "passive"))
      (node (ref "LED3") (pin "7") (pinfunction "A_7") (pintype "passive"))
      (node (ref "LED4") (pin "7") (pinfunction "A_7") (pintype "passive"))
      (node (ref "LED5") (pin "7") (pinfunction "A_7") (pintype "passive"))
      (node (ref "LED6") (pin "7") (pinfunction "A_7") (pintype "passive"))
      (node (ref "LED7") (pin "7") (pinfunction "A_7") (pintype "passive"))
      (node (ref "LED8") (pin "7") (pinfunction "A_7") (pintype "passive"))
      (node (ref "LED9") (pin "7") (pinfunction "A_7") (pintype "passive"))
      (node (ref "X12") (pin "8") (pinfunction "S_8") (pintype "passive"))
    )
    (net (code "105") (name "R1B") (class "Default")
      (node (ref "LED1") (pin "6") (pinfunction "B_6") (pintype "passive"))
      (node (ref "LED10") (pin "6") (pinfunction "B_6") (pintype "passive"))
      (node (ref "LED2") (pin "6") (pinfunction "B_6") (pintype "passive"))
      (node (ref "LED3") (pin "6") (pinfunction "B_6") (pintype "passive"))
      (node (ref "LED4") (pin "6") (pinfunction "B_6") (pintype "passive"))
      (node (ref "LED5") (pin "6") (pinfunction "B_6") (pintype "passive"))
      (node (ref "LED6") (pin "6") (pinfunction "B_6") (pintype "passive"))
      (node (ref "LED7") (pin "6") (pinfunction "B_6") (pintype "passive"))
      (node (ref "LED8") (pin "6") (pinfunction "B_6") (pintype "passive"))
      (node (ref "LED9") (pin "6") (pinfunction "B_6") (pintype "passive"))
      (node (ref "X12") (pin "7") (pinfunction "S_7") (pintype "passive"))
    )
    (net (code "106") (name "R1C") (class "Default")
      (node (ref "LED1") (pin "4") (pinfunction "C_4") (pintype "passive"))
      (node (ref "LED10") (pin "4") (pinfunction "C_4") (pintype "passive"))
      (node (ref "LED2") (pin "4") (pinfunction "C_4") (pintype "passive"))
      (node (ref "LED3") (pin "4") (pinfunction "C_4") (pintype "passive"))
      (node (ref "LED4") (pin "4") (pinfunction "C_4") (pintype "passive"))
      (node (ref "LED5") (pin "4") (pinfunction "C_4") (pintype "passive"))
      (node (ref "LED6") (pin "4") (pinfunction "C_4") (pintype "passive"))
      (node (ref "LED7") (pin "4") (pinfunction "C_4") (pintype "passive"))
      (node (ref "LED8") (pin "4") (pinfunction "C_4") (pintype "passive"))
      (node (ref "LED9") (pin "4") (pinfunction "C_4") (pintype "passive"))
      (node (ref "X12") (pin "6") (pinfunction "S_6") (pintype "passive"))
    )
    (net (code "107") (name "R1D") (class "Default")
      (node (ref "LED1") (pin "2") (pinfunction "D_2") (pintype "passive"))
      (node (ref "LED10") (pin "2") (pinfunction "D_2") (pintype "passive"))
      (node (ref "LED2") (pin "2") (pinfunction "D_2") (pintype "passive"))
      (node (ref "LED3") (pin "2") (pinfunction "D_2") (pintype "passive"))
      (node (ref "LED4") (pin "2") (pinfunction "D_2") (pintype "passive"))
      (node (ref "LED5") (pin "2") (pinfunction "D_2") (pintype "passive"))
      (node (ref "LED6") (pin "2") (pinfunction "D_2") (pintype "passive"))
      (node (ref "LED7") (pin "2") (pinfunction "D_2") (pintype "passive"))
      (node (ref "LED8") (pin "2") (pinfunction "D_2") (pintype "passive"))
      (node (ref "LED9") (pin "2") (pinfunction "D_2") (pintype "passive"))
      (node (ref "X12") (pin "5") (pinfunction "S_5") (pintype "passive"))
    )
    (net (code "108") (name "R1E") (class "Default")
      (node (ref "LED1") (pin "1") (pinfunction "E_1") (pintype "passive"))
      (node (ref "LED10") (pin "1") (pinfunction "E_1") (pintype "passive"))
      (node (ref "LED2") (pin "1") (pinfunction "E_1") (pintype "passive"))
      (node (ref "LED3") (pin "1") (pinfunction "E_1") (pintype "passive"))
      (node (ref "LED4") (pin "1") (pinfunction "E_1") (pintype "passive"))
      (node (ref "LED5") (pin "1") (pinfunction "E_1") (pintype "passive"))
      (node (ref "LED6") (pin "1") (pinfunction "E_1") (pintype "passive"))
      (node (ref "LED7") (pin "1") (pinfunction "E_1") (pintype "passive"))
      (node (ref "LED8") (pin "1") (pinfunction "E_1") (pintype "passive"))
      (node (ref "LED9") (pin "1") (pinfunction "E_1") (pintype "passive"))
      (node (ref "X12") (pin "4") (pinfunction "S_4") (pintype "passive"))
    )
    (net (code "109") (name "R1F") (class "Default")
      (node (ref "LED1") (pin "9") (pinfunction "F_9") (pintype "passive"))
      (node (ref "LED10") (pin "9") (pinfunction "F_9") (pintype "passive"))
      (node (ref "LED2") (pin "9") (pinfunction "F_9") (pintype "passive"))
      (node (ref "LED3") (pin "9") (pinfunction "F_9") (pintype "passive"))
      (node (ref "LED4") (pin "9") (pinfunction "F_9") (pintype "passive"))
      (node (ref "LED5") (pin "9") (pinfunction "F_9") (pintype "passive"))
      (node (ref "LED6") (pin "9") (pinfunction "F_9") (pintype "passive"))
      (node (ref "LED7") (pin "9") (pinfunction "F_9") (pintype "passive"))
      (node (ref "LED8") (pin "9") (pinfunction "F_9") (pintype "passive"))
      (node (ref "LED9") (pin "9") (pinfunction "F_9") (pintype "passive"))
      (node (ref "X12") (pin "3") (pinfunction "S_3") (pintype "passive"))
    )
    (net (code "110") (name "R1G") (class "Default")
      (node (ref "LED1") (pin "10") (pinfunction "G_10") (pintype "passive"))
      (node (ref "LED10") (pin "10") (pinfunction "G_10") (pintype "passive"))
      (node (ref "LED2") (pin "10") (pinfunction "G_10") (pintype "passive"))
      (node (ref "LED3") (pin "10") (pinfunction "G_10") (pintype "passive"))
      (node (ref "LED4") (pin "10") (pinfunction "G_10") (pintype "passive"))
      (node (ref "LED5") (pin "10") (pinfunction "G_10") (pintype "passive"))
      (node (ref "LED6") (pin "10") (pinfunction "G_10") (pintype "passive"))
      (node (ref "LED7") (pin "10") (pinfunction "G_10") (pintype "passive"))
      (node (ref "LED8") (pin "10") (pinfunction "G_10") (pintype "passive"))
      (node (ref "LED9") (pin "10") (pinfunction "G_10") (pintype "passive"))
      (node (ref "X12") (pin "2") (pinfunction "S_2") (pintype "passive"))
    )
    (net (code "111") (name "R1H") (class "Default")
      (node (ref "LED1") (pin "5") (pinfunction "DP_5") (pintype "passive"))
      (node (ref "LED10") (pin "5") (pinfunction "DP_5") (pintype "passive"))
      (node (ref "LED2") (pin "5") (pinfunction "DP_5") (pintype "passive"))
      (node (ref "LED3") (pin "5") (pinfunction "DP_5") (pintype "passive"))
      (node (ref "LED4") (pin "5") (pinfunction "DP_5") (pintype "passive"))
      (node (ref "LED5") (pin "5") (pinfunction "DP_5") (pintype "passive"))
      (node (ref "LED6") (pin "5") (pinfunction "DP_5") (pintype "passive"))
      (node (ref "LED7") (pin "5") (pinfunction "DP_5") (pintype "passive"))
      (node (ref "LED8") (pin "5") (pinfunction "DP_5") (pintype "passive"))
      (node (ref "LED9") (pin "5") (pinfunction "DP_5") (pintype "passive"))
      (node (ref "X12") (pin "1") (pinfunction "S_1") (pintype "passive"))
    )
    (net (code "112") (name "R2A") (class "Default")
      (node (ref "LED11") (pin "7") (pinfunction "A_7") (pintype "passive"))
      (node (ref "LED12") (pin "7") (pinfunction "A_7") (pintype "passive"))
      (node (ref "LED13") (pin "7") (pinfunction "A_7") (pintype "passive"))
      (node (ref "LED14") (pin "7") (pinfunction "A_7") (pintype "passive"))
      (node (ref "LED15") (pin "7") (pinfunction "A_7") (pintype "passive"))
      (node (ref "LED16") (pin "7") (pinfunction "A_7") (pintype "passive"))
      (node (ref "LED17") (pin "7") (pinfunction "A_7") (pintype "passive"))
      (node (ref "LED18") (pin "7") (pinfunction "A_7") (pintype "passive"))
      (node (ref "LED19") (pin "7") (pinfunction "A_7") (pintype "passive"))
      (node (ref "LED20") (pin "7") (pinfunction "A_7") (pintype "passive"))
      (node (ref "X13") (pin "8") (pinfunction "S_8") (pintype "passive"))
    )
    (net (code "113") (name "R2B") (class "Default")
      (node (ref "LED11") (pin "6") (pinfunction "B_6") (pintype "passive"))
      (node (ref "LED12") (pin "6") (pinfunction "B_6") (pintype "passive"))
      (node (ref "LED13") (pin "6") (pinfunction "B_6") (pintype "passive"))
      (node (ref "LED14") (pin "6") (pinfunction "B_6") (pintype "passive"))
      (node (ref "LED15") (pin "6") (pinfunction "B_6") (pintype "passive"))
      (node (ref "LED16") (pin "6") (pinfunction "B_6") (pintype "passive"))
      (node (ref "LED17") (pin "6") (pinfunction "B_6") (pintype "passive"))
      (node (ref "LED18") (pin "6") (pinfunction "B_6") (pintype "passive"))
      (node (ref "LED19") (pin "6") (pinfunction "B_6") (pintype "passive"))
      (node (ref "LED20") (pin "6") (pinfunction "B_6") (pintype "passive"))
      (node (ref "X13") (pin "7") (pinfunction "S_7") (pintype "passive"))
    )
    (net (code "114") (name "R2C") (class "Default")
      (node (ref "LED11") (pin "4") (pinfunction "C_4") (pintype "passive"))
      (node (ref "LED12") (pin "4") (pinfunction "C_4") (pintype "passive"))
      (node (ref "LED13") (pin "4") (pinfunction "C_4") (pintype "passive"))
      (node (ref "LED14") (pin "4") (pinfunction "C_4") (pintype "passive"))
      (node (ref "LED15") (pin "4") (pinfunction "C_4") (pintype "passive"))
      (node (ref "LED16") (pin "4") (pinfunction "C_4") (pintype "passive"))
      (node (ref "LED17") (pin "4") (pinfunction "C_4") (pintype "passive"))
      (node (ref "LED18") (pin "4") (pinfunction "C_4") (pintype "passive"))
      (node (ref "LED19") (pin "4") (pinfunction "C_4") (pintype "passive"))
      (node (ref "LED20") (pin "4") (pinfunction "C_4") (pintype "passive"))
      (node (ref "X13") (pin "6") (pinfunction "S_6") (pintype "passive"))
    )
    (net (code "115") (name "R2D") (class "Default")
      (node (ref "LED11") (pin "2") (pinfunction "D_2") (pintype "passive"))
      (node (ref "LED12") (pin "2") (pinfunction "D_2") (pintype "passive"))
      (node (ref "LED13") (pin "2") (pinfunction "D_2") (pintype "passive"))
      (node (ref "LED14") (pin "2") (pinfunction "D_2") (pintype "passive"))
      (node (ref "LED15") (pin "2") (pinfunction "D_2") (pintype "passive"))
      (node (ref "LED16") (pin "2") (pinfunction "D_2") (pintype "passive"))
      (node (ref "LED17") (pin "2") (pinfunction "D_2") (pintype "passive"))
      (node (ref "LED18") (pin "2") (pinfunction "D_2") (pintype "passive"))
      (node (ref "LED19") (pin "2") (pinfunction "D_2") (pintype "passive"))
      (node (ref "LED20") (pin "2") (pinfunction "D_2") (pintype "passive"))
      (node (ref "X13") (pin "5") (pinfunction "S_5") (pintype "passive"))
    )
    (net (code "116") (name "R2E") (class "Default")
      (node (ref "LED11") (pin "1") (pinfunction "E_1") (pintype "passive"))
      (node (ref "LED12") (pin "1") (pinfunction "E_1") (pintype "passive"))
      (node (ref "LED13") (pin "1") (pinfunction "E_1") (pintype "passive"))
      (node (ref "LED14") (pin "1") (pinfunction "E_1") (pintype "passive"))
      (node (ref "LED15") (pin "1") (pinfunction "E_1") (pintype "passive"))
      (node (ref "LED16") (pin "1") (pinfunction "E_1") (pintype "passive"))
      (node (ref "LED17") (pin "1") (pinfunction "E_1") (pintype "passive"))
      (node (ref "LED18") (pin "1") (pinfunction "E_1") (pintype "passive"))
      (node (ref "LED19") (pin "1") (pinfunction "E_1") (pintype "passive"))
      (node (ref "LED20") (pin "1") (pinfunction "E_1") (pintype "passive"))
      (node (ref "X13") (pin "4") (pinfunction "S_4") (pintype "passive"))
    )
    (net (code "117") (name "R2F") (class "Default")
      (node (ref "LED11") (pin "9") (pinfunction "F_9") (pintype "passive"))
      (node (ref "LED12") (pin "9") (pinfunction "F_9") (pintype "passive"))
      (node (ref "LED13") (pin "9") (pinfunction "F_9") (pintype "passive"))
      (node (ref "LED14") (pin "9") (pinfunction "F_9") (pintype "passive"))
      (node (ref "LED15") (pin "9") (pinfunction "F_9") (pintype "passive"))
      (node (ref "LED16") (pin "9") (pinfunction "F_9") (pintype "passive"))
      (node (ref "LED17") (pin "9") (pinfunction "F_9") (pintype "passive"))
      (node (ref "LED18") (pin "9") (pinfunction "F_9") (pintype "passive"))
      (node (ref "LED19") (pin "9") (pinfunction "F_9") (pintype "passive"))
      (node (ref "LED20") (pin "9") (pinfunction "F_9") (pintype "passive"))
      (node (ref "X13") (pin "3") (pinfunction "S_3") (pintype "passive"))
    )
    (net (code "118") (name "R2G") (class "Default")
      (node (ref "LED11") (pin "10") (pinfunction "G_10") (pintype "passive"))
      (node (ref "LED12") (pin "10") (pinfunction "G_10") (pintype "passive"))
      (node (ref "LED13") (pin "10") (pinfunction "G_10") (pintype "passive"))
      (node (ref "LED14") (pin "10") (pinfunction "G_10") (pintype "passive"))
      (node (ref "LED15") (pin "10") (pinfunction "G_10") (pintype "passive"))
      (node (ref "LED16") (pin "10") (pinfunction "G_10") (pintype "passive"))
      (node (ref "LED17") (pin "10") (pinfunction "G_10") (pintype "passive"))
      (node (ref "LED18") (pin "10") (pinfunction "G_10") (pintype "passive"))
      (node (ref "LED19") (pin "10") (pinfunction "G_10") (pintype "passive"))
      (node (ref "LED20") (pin "10") (pinfunction "G_10") (pintype "passive"))
      (node (ref "X13") (pin "2") (pinfunction "S_2") (pintype "passive"))
    )
    (net (code "119") (name "R2H") (class "Default")
      (node (ref "LED11") (pin "5") (pinfunction "DP_5") (pintype "passive"))
      (node (ref "LED12") (pin "5") (pinfunction "DP_5") (pintype "passive"))
      (node (ref "LED13") (pin "5") (pinfunction "DP_5") (pintype "passive"))
      (node (ref "LED14") (pin "5") (pinfunction "DP_5") (pintype "passive"))
      (node (ref "LED15") (pin "5") (pinfunction "DP_5") (pintype "passive"))
      (node (ref "LED16") (pin "5") (pinfunction "DP_5") (pintype "passive"))
      (node (ref "LED17") (pin "5") (pinfunction "DP_5") (pintype "passive"))
      (node (ref "LED18") (pin "5") (pinfunction "DP_5") (pintype "passive"))
      (node (ref "LED19") (pin "5") (pinfunction "DP_5") (pintype "passive"))
      (node (ref "LED20") (pin "5") (pinfunction "DP_5") (pintype "passive"))
      (node (ref "X13") (pin "1") (pinfunction "S_1") (pintype "passive"))
    )
    (net (code "120") (name "R3A") (class "Default")
      (node (ref "LED21") (pin "7") (pinfunction "A_7") (pintype "passive"))
      (node (ref "LED22") (pin "7") (pinfunction "A_7") (pintype "passive"))
      (node (ref "LED23") (pin "7") (pinfunction "A_7") (pintype "passive"))
      (node (ref "LED24") (pin "7") (pinfunction "A_7") (pintype "passive"))
      (node (ref "LED25") (pin "7") (pinfunction "A_7") (pintype "passive"))
      (node (ref "LED26") (pin "7") (pinfunction "A_7") (pintype "passive"))
      (node (ref "LED27") (pin "7") (pinfunction "A_7") (pintype "passive"))
      (node (ref "LED28") (pin "7") (pinfunction "A_7") (pintype "passive"))
      (node (ref "LED29") (pin "7") (pinfunction "A_7") (pintype "passive"))
      (node (ref "LED30") (pin "7") (pinfunction "A_7") (pintype "passive"))
      (node (ref "X14") (pin "8") (pinfunction "S_8") (pintype "passive"))
    )
    (net (code "121") (name "R3B") (class "Default")
      (node (ref "LED21") (pin "6") (pinfunction "B_6") (pintype "passive"))
      (node (ref "LED22") (pin "6") (pinfunction "B_6") (pintype "passive"))
      (node (ref "LED23") (pin "6") (pinfunction "B_6") (pintype "passive"))
      (node (ref "LED24") (pin "6") (pinfunction "B_6") (pintype "passive"))
      (node (ref "LED25") (pin "6") (pinfunction "B_6") (pintype "passive"))
      (node (ref "LED26") (pin "6") (pinfunction "B_6") (pintype "passive"))
      (node (ref "LED27") (pin "6") (pinfunction "B_6") (pintype "passive"))
      (node (ref "LED28") (pin "6") (pinfunction "B_6") (pintype "passive"))
      (node (ref "LED29") (pin "6") (pinfunction "B_6") (pintype "passive"))
      (node (ref "LED30") (pin "6") (pinfunction "B_6") (pintype "passive"))
      (node (ref "X14") (pin "7") (pinfunction "S_7") (pintype "passive"))
    )
    (net (code "122") (name "R3C") (class "Default")
      (node (ref "LED21") (pin "4") (pinfunction "C_4") (pintype "passive"))
      (node (ref "LED22") (pin "4") (pinfunction "C_4") (pintype "passive"))
      (node (ref "LED23") (pin "4") (pinfunction "C_4") (pintype "passive"))
      (node (ref "LED24") (pin "4") (pinfunction "C_4") (pintype "passive"))
      (node (ref "LED25") (pin "4") (pinfunction "C_4") (pintype "passive"))
      (node (ref "LED26") (pin "4") (pinfunction "C_4") (pintype "passive"))
      (node (ref "LED27") (pin "4") (pinfunction "C_4") (pintype "passive"))
      (node (ref "LED28") (pin "4") (pinfunction "C_4") (pintype "passive"))
      (node (ref "LED29") (pin "4") (pinfunction "C_4") (pintype "passive"))
      (node (ref "LED30") (pin "4") (pinfunction "C_4") (pintype "passive"))
      (node (ref "X14") (pin "6") (pinfunction "S_6") (pintype "passive"))
    )
    (net (code "123") (name "R3D") (class "Default")
      (node (ref "LED21") (pin "2") (pinfunction "D_2") (pintype "passive"))
      (node (ref "LED22") (pin "2") (pinfunction "D_2") (pintype "passive"))
      (node (ref "LED23") (pin "2") (pinfunction "D_2") (pintype "passive"))
      (node (ref "LED24") (pin "2") (pinfunction "D_2") (pintype "passive"))
      (node (ref "LED25") (pin "2") (pinfunction "D_2") (pintype "passive"))
      (node (ref "LED26") (pin "2") (pinfunction "D_2") (pintype "passive"))
      (node (ref "LED27") (pin "2") (pinfunction "D_2") (pintype "passive"))
      (node (ref "LED28") (pin "2") (pinfunction "D_2") (pintype "passive"))
      (node (ref "LED29") (pin "2") (pinfunction "D_2") (pintype "passive"))
      (node (ref "LED30") (pin "2") (pinfunction "D_2") (pintype "passive"))
      (node (ref "X14") (pin "5") (pinfunction "S_5") (pintype "passive"))
    )
    (net (code "124") (name "R3E") (class "Default")
      (node (ref "LED21") (pin "1") (pinfunction "E_1") (pintype "passive"))
      (node (ref "LED22") (pin "1") (pinfunction "E_1") (pintype "passive"))
      (node (ref "LED23") (pin "1") (pinfunction "E_1") (pintype "passive"))
      (node (ref "LED24") (pin "1") (pinfunction "E_1") (pintype "passive"))
      (node (ref "LED25") (pin "1") (pinfunction "E_1") (pintype "passive"))
      (node (ref "LED26") (pin "1") (pinfunction "E_1") (pintype "passive"))
      (node (ref "LED27") (pin "1") (pinfunction "E_1") (pintype "passive"))
      (node (ref "LED28") (pin "1") (pinfunction "E_1") (pintype "passive"))
      (node (ref "LED29") (pin "1") (pinfunction "E_1") (pintype "passive"))
      (node (ref "LED30") (pin "1") (pinfunction "E_1") (pintype "passive"))
      (node (ref "X14") (pin "4") (pinfunction "S_4") (pintype "passive"))
    )
    (net (code "125") (name "R3F") (class "Default")
      (node (ref "LED21") (pin "9") (pinfunction "F_9") (pintype "passive"))
      (node (ref "LED22") (pin "9") (pinfunction "F_9") (pintype "passive"))
      (node (ref "LED23") (pin "9") (pinfunction "F_9") (pintype "passive"))
      (node (ref "LED24") (pin "9") (pinfunction "F_9") (pintype "passive"))
      (node (ref "LED25") (pin "9") (pinfunction "F_9") (pintype "passive"))
      (node (ref "LED26") (pin "9") (pinfunction "F_9") (pintype "passive"))
      (node (ref "LED27") (pin "9") (pinfunction "F_9") (pintype "passive"))
      (node (ref "LED28") (pin "9") (pinfunction "F_9") (pintype "passive"))
      (node (ref "LED29") (pin "9") (pinfunction "F_9") (pintype "passive"))
      (node (ref "LED30") (pin "9") (pinfunction "F_9") (pintype "passive"))
      (node (ref "X14") (pin "3") (pinfunction "S_3") (pintype "passive"))
    )
    (net (code "126") (name "R3G") (class "Default")
      (node (ref "LED21") (pin "10") (pinfunction "G_10") (pintype "passive"))
      (node (ref "LED22") (pin "10") (pinfunction "G_10") (pintype "passive"))
      (node (ref "LED23") (pin "10") (pinfunction "G_10") (pintype "passive"))
      (node (ref "LED24") (pin "10") (pinfunction "G_10") (pintype "passive"))
      (node (ref "LED25") (pin "10") (pinfunction "G_10") (pintype "passive"))
      (node (ref "LED26") (pin "10") (pinfunction "G_10") (pintype "passive"))
      (node (ref "LED27") (pin "10") (pinfunction "G_10") (pintype "passive"))
      (node (ref "LED28") (pin "10") (pinfunction "G_10") (pintype "passive"))
      (node (ref "LED29") (pin "10") (pinfunction "G_10") (pintype "passive"))
      (node (ref "LED30") (pin "10") (pinfunction "G_10") (pintype "passive"))
      (node (ref "X14") (pin "2") (pinfunction "S_2") (pintype "passive"))
    )
    (net (code "127") (name "R3H") (class "Default")
      (node (ref "LED21") (pin "5") (pinfunction "DP_5") (pintype "passive"))
      (node (ref "LED22") (pin "5") (pinfunction "DP_5") (pintype "passive"))
      (node (ref "LED23") (pin "5") (pinfunction "DP_5") (pintype "passive"))
      (node (ref "LED24") (pin "5") (pinfunction "DP_5") (pintype "passive"))
      (node (ref "LED25") (pin "5") (pinfunction "DP_5") (pintype "passive"))
      (node (ref "LED26") (pin "5") (pinfunction "DP_5") (pintype "passive"))
      (node (ref "LED27") (pin "5") (pinfunction "DP_5") (pintype "passive"))
      (node (ref "LED28") (pin "5") (pinfunction "DP_5") (pintype "passive"))
      (node (ref "LED29") (pin "5") (pinfunction "DP_5") (pintype "passive"))
      (node (ref "LED30") (pin "5") (pinfunction "DP_5") (pintype "passive"))
      (node (ref "X14") (pin "1") (pinfunction "S_1") (pintype "passive"))
    )
    (net (code "128") (name "R4A") (class "Default")
      (node (ref "LED31") (pin "7") (pinfunction "A_7") (pintype "passive"))
      (node (ref "LED32") (pin "7") (pinfunction "A_7") (pintype "passive"))
      (node (ref "LED33") (pin "7") (pinfunction "A_7") (pintype "passive"))
      (node (ref "LED34") (pin "7") (pinfunction "A_7") (pintype "passive"))
      (node (ref "LED35") (pin "7") (pinfunction "A_7") (pintype "passive"))
      (node (ref "LED36") (pin "7") (pinfunction "A_7") (pintype "passive"))
      (node (ref "LED37") (pin "7") (pinfunction "A_7") (pintype "passive"))
      (node (ref "LED38") (pin "7") (pinfunction "A_7") (pintype "passive"))
      (node (ref "LED39") (pin "7") (pinfunction "A_7") (pintype "passive"))
      (node (ref "LED40") (pin "7") (pinfunction "A_7") (pintype "passive"))
      (node (ref "X15") (pin "8") (pinfunction "S_8") (pintype "passive"))
    )
    (net (code "129") (name "R4B") (class "Default")
      (node (ref "LED31") (pin "6") (pinfunction "B_6") (pintype "passive"))
      (node (ref "LED32") (pin "6") (pinfunction "B_6") (pintype "passive"))
      (node (ref "LED33") (pin "6") (pinfunction "B_6") (pintype "passive"))
      (node (ref "LED34") (pin "6") (pinfunction "B_6") (pintype "passive"))
      (node (ref "LED35") (pin "6") (pinfunction "B_6") (pintype "passive"))
      (node (ref "LED36") (pin "6") (pinfunction "B_6") (pintype "passive"))
      (node (ref "LED37") (pin "6") (pinfunction "B_6") (pintype "passive"))
      (node (ref "LED38") (pin "6") (pinfunction "B_6") (pintype "passive"))
      (node (ref "LED39") (pin "6") (pinfunction "B_6") (pintype "passive"))
      (node (ref "LED40") (pin "6") (pinfunction "B_6") (pintype "passive"))
      (node (ref "X15") (pin "7") (pinfunction "S_7") (pintype "passive"))
    )
    (net (code "130") (name "R4C") (class "Default")
      (node (ref "LED31") (pin "4") (pinfunction "C_4") (pintype "passive"))
      (node (ref "LED32") (pin "4") (pinfunction "C_4") (pintype "passive"))
      (node (ref "LED33") (pin "4") (pinfunction "C_4") (pintype "passive"))
      (node (ref "LED34") (pin "4") (pinfunction "C_4") (pintype "passive"))
      (node (ref "LED35") (pin "4") (pinfunction "C_4") (pintype "passive"))
      (node (ref "LED36") (pin "4") (pinfunction "C_4") (pintype "passive"))
      (node (ref "LED37") (pin "4") (pinfunction "C_4") (pintype "passive"))
      (node (ref "LED38") (pin "4") (pinfunction "C_4") (pintype "passive"))
      (node (ref "LED39") (pin "4") (pinfunction "C_4") (pintype "passive"))
      (node (ref "LED40") (pin "4") (pinfunction "C_4") (pintype "passive"))
      (node (ref "X15") (pin "6") (pinfunction "S_6") (pintype "passive"))
    )
    (net (code "131") (name "R4D") (class "Default")
      (node (ref "LED31") (pin "2") (pinfunction "D_2") (pintype "passive"))
      (node (ref "LED32") (pin "2") (pinfunction "D_2") (pintype "passive"))
      (node (ref "LED33") (pin "2") (pinfunction "D_2") (pintype "passive"))
      (node (ref "LED34") (pin "2") (pinfunction "D_2") (pintype "passive"))
      (node (ref "LED35") (pin "2") (pinfunction "D_2") (pintype "passive"))
      (node (ref "LED36") (pin "2") (pinfunction "D_2") (pintype "passive"))
      (node (ref "LED37") (pin "2") (pinfunction "D_2") (pintype "passive"))
      (node (ref "LED38") (pin "2") (pinfunction "D_2") (pintype "passive"))
      (node (ref "LED39") (pin "2") (pinfunction "D_2") (pintype "passive"))
      (node (ref "LED40") (pin "2") (pinfunction "D_2") (pintype "passive"))
      (node (ref "X15") (pin "5") (pinfunction "S_5") (pintype "passive"))
    )
    (net (code "132") (name "R4E") (class "Default")
      (node (ref "LED31") (pin "1") (pinfunction "E_1") (pintype "passive"))
      (node (ref "LED32") (pin "1") (pinfunction "E_1") (pintype "passive"))
      (node (ref "LED33") (pin "1") (pinfunction "E_1") (pintype "passive"))
      (node (ref "LED34") (pin "1") (pinfunction "E_1") (pintype "passive"))
      (node (ref "LED35") (pin "1") (pinfunction "E_1") (pintype "passive"))
      (node (ref "LED36") (pin "1") (pinfunction "E_1") (pintype "passive"))
      (node (ref "LED37") (pin "1") (pinfunction "E_1") (pintype "passive"))
      (node (ref "LED38") (pin "1") (pinfunction "E_1") (pintype "passive"))
      (node (ref "LED39") (pin "1") (pinfunction "E_1") (pintype "passive"))
      (node (ref "LED40") (pin "1") (pinfunction "E_1") (pintype "passive"))
      (node (ref "X15") (pin "4") (pinfunction "S_4") (pintype "passive"))
    )
    (net (code "133") (name "R4F") (class "Default")
      (node (ref "LED31") (pin "9") (pinfunction "F_9") (pintype "passive"))
      (node (ref "LED32") (pin "9") (pinfunction "F_9") (pintype "passive"))
      (node (ref "LED33") (pin "9") (pinfunction "F_9") (pintype "passive"))
      (node (ref "LED34") (pin "9") (pinfunction "F_9") (pintype "passive"))
      (node (ref "LED35") (pin "9") (pinfunction "F_9") (pintype "passive"))
      (node (ref "LED36") (pin "9") (pinfunction "F_9") (pintype "passive"))
      (node (ref "LED37") (pin "9") (pinfunction "F_9") (pintype "passive"))
      (node (ref "LED38") (pin "9") (pinfunction "F_9") (pintype "passive"))
      (node (ref "LED39") (pin "9") (pinfunction "F_9") (pintype "passive"))
      (node (ref "LED40") (pin "9") (pinfunction "F_9") (pintype "passive"))
      (node (ref "X15") (pin "3") (pinfunction "S_3") (pintype "passive"))
    )
    (net (code "134") (name "R4G") (class "Default")
      (node (ref "LED31") (pin "10") (pinfunction "G_10") (pintype "passive"))
      (node (ref "LED32") (pin "10") (pinfunction "G_10") (pintype "passive"))
      (node (ref "LED33") (pin "10") (pinfunction "G_10") (pintype "passive"))
      (node (ref "LED34") (pin "10") (pinfunction "G_10") (pintype "passive"))
      (node (ref "LED35") (pin "10") (pinfunction "G_10") (pintype "passive"))
      (node (ref "LED36") (pin "10") (pinfunction "G_10") (pintype "passive"))
      (node (ref "LED37") (pin "10") (pinfunction "G_10") (pintype "passive"))
      (node (ref "LED38") (pin "10") (pinfunction "G_10") (pintype "passive"))
      (node (ref "LED39") (pin "10") (pinfunction "G_10") (pintype "passive"))
      (node (ref "LED40") (pin "10") (pinfunction "G_10") (pintype "passive"))
      (node (ref "X15") (pin "2") (pinfunction "S_2") (pintype "passive"))
    )
    (net (code "135") (name "R4H") (class "Default")
      (node (ref "LED31") (pin "5") (pinfunction "DP_5") (pintype "passive"))
      (node (ref "LED32") (pin "5") (pinfunction "DP_5") (pintype "passive"))
      (node (ref "LED33") (pin "5") (pinfunction "DP_5") (pintype "passive"))
      (node (ref "LED34") (pin "5") (pinfunction "DP_5") (pintype "passive"))
      (node (ref "LED35") (pin "5") (pinfunction "DP_5") (pintype "passive"))
      (node (ref "LED36") (pin "5") (pinfunction "DP_5") (pintype "passive"))
      (node (ref "LED37") (pin "5") (pinfunction "DP_5") (pintype "passive"))
      (node (ref "LED38") (pin "5") (pinfunction "DP_5") (pintype "passive"))
      (node (ref "LED39") (pin "5") (pinfunction "DP_5") (pintype "passive"))
      (node (ref "LED40") (pin "5") (pinfunction "DP_5") (pintype "passive"))
      (node (ref "X15") (pin "1") (pinfunction "S_1") (pintype "passive"))
    )
    (net (code "136") (name "SEG1") (class "Default")
      (node (ref "LED1") (pin "8") (pinfunction "COM_8") (pintype "passive"))
      (node (ref "X2") (pin "10") (pinfunction "S_10") (pintype "passive"))
    )
    (net (code "137") (name "SEG2") (class "Default")
      (node (ref "LED2") (pin "8") (pinfunction "COM_8") (pintype "passive"))
      (node (ref "X2") (pin "9") (pinfunction "S_9") (pintype "passive"))
    )
    (net (code "138") (name "SEG3") (class "Default")
      (node (ref "LED3") (pin "8") (pinfunction "COM_8") (pintype "passive"))
      (node (ref "X2") (pin "8") (pinfunction "S_8") (pintype "passive"))
    )
    (net (code "139") (name "SEG4") (class "Default")
      (node (ref "LED4") (pin "8") (pinfunction "COM_8") (pintype "passive"))
      (node (ref "X2") (pin "7") (pinfunction "S_7") (pintype "passive"))
    )
    (net (code "140") (name "SEG5") (class "Default")
      (node (ref "LED5") (pin "8") (pinfunction "COM_8") (pintype "passive"))
      (node (ref "X2") (pin "6") (pinfunction "S_6") (pintype "passive"))
    )
    (net (code "141") (name "SEG6") (class "Default")
      (node (ref "LED6") (pin "8") (pinfunction "COM_8") (pintype "passive"))
      (node (ref "X2") (pin "5") (pinfunction "S_5") (pintype "passive"))
    )
    (net (code "142") (name "SEG7") (class "Default")
      (node (ref "LED7") (pin "8") (pinfunction "COM_8") (pintype "passive"))
      (node (ref "X2") (pin "4") (pinfunction "S_4") (pintype "passive"))
    )
    (net (code "143") (name "SEG8") (class "Default")
      (node (ref "LED8") (pin "8") (pinfunction "COM_8") (pintype "passive"))
      (node (ref "X2") (pin "3") (pinfunction "S_3") (pintype "passive"))
    )
    (net (code "144") (name "SEG9") (class "Default")
      (node (ref "LED9") (pin "8") (pinfunction "COM_8") (pintype "passive"))
      (node (ref "X2") (pin "2") (pinfunction "S_2") (pintype "passive"))
    )
    (net (code "145") (name "SEG10") (class "Default")
      (node (ref "LED10") (pin "8") (pinfunction "COM_8") (pintype "passive"))
      (node (ref "X2") (pin "1") (pinfunction "S_1") (pintype "passive"))
    )
    (net (code "146") (name "SEG11") (class "Default")
      (node (ref "LED11") (pin "8") (pinfunction "COM_8") (pintype "passive"))
      (node (ref "X3") (pin "10") (pinfunction "S_10") (pintype "passive"))
    )
    (net (code "147") (name "SEG12") (class "Default")
      (node (ref "LED12") (pin "8") (pinfunction "COM_8") (pintype "passive"))
      (node (ref "X3") (pin "9") (pinfunction "S_9") (pintype "passive"))
    )
    (net (code "148") (name "SEG13") (class "Default")
      (node (ref "LED13") (pin "8") (pinfunction "COM_8") (pintype "passive"))
      (node (ref "X3") (pin "8") (pinfunction "S_8") (pintype "passive"))
    )
    (net (code "149") (name "SEG14") (class "Default")
      (node (ref "LED14") (pin "8") (pinfunction "COM_8") (pintype "passive"))
      (node (ref "X3") (pin "7") (pinfunction "S_7") (pintype "passive"))
    )
    (net (code "150") (name "SEG15") (class "Default")
      (node (ref "LED15") (pin "8") (pinfunction "COM_8") (pintype "passive"))
      (node (ref "X3") (pin "6") (pinfunction "S_6") (pintype "passive"))
    )
    (net (code "151") (name "SEG16") (class "Default")
      (node (ref "LED16") (pin "8") (pinfunction "COM_8") (pintype "passive"))
      (node (ref "X3") (pin "5") (pinfunction "S_5") (pintype "passive"))
    )
    (net (code "152") (name "SEG17") (class "Default")
      (node (ref "LED17") (pin "8") (pinfunction "COM_8") (pintype "passive"))
      (node (ref "X3") (pin "4") (pinfunction "S_4") (pintype "passive"))
    )
    (net (code "153") (name "SEG18") (class "Default")
      (node (ref "LED18") (pin "8") (pinfunction "COM_8") (pintype "passive"))
      (node (ref "X3") (pin "3") (pinfunction "S_3") (pintype "passive"))
    )
    (net (code "154") (name "SEG19") (class "Default")
      (node (ref "LED19") (pin "8") (pinfunction "COM_8") (pintype "passive"))
      (node (ref "X3") (pin "2") (pinfunction "S_2") (pintype "passive"))
    )
    (net (code "155") (name "SEG20") (class "Default")
      (node (ref "LED20") (pin "8") (pinfunction "COM_8") (pintype "passive"))
      (node (ref "X3") (pin "1") (pinfunction "S_1") (pintype "passive"))
    )
    (net (code "156") (name "SEG21") (class "Default")
      (node (ref "LED21") (pin "8") (pinfunction "COM_8") (pintype "passive"))
      (node (ref "X4") (pin "10") (pinfunction "S_10") (pintype "passive"))
    )
    (net (code "157") (name "SEG22") (class "Default")
      (node (ref "LED22") (pin "8") (pinfunction "COM_8") (pintype "passive"))
      (node (ref "X4") (pin "9") (pinfunction "S_9") (pintype "passive"))
    )
    (net (code "158") (name "SEG23") (class "Default")
      (node (ref "LED23") (pin "8") (pinfunction "COM_8") (pintype "passive"))
      (node (ref "X4") (pin "8") (pinfunction "S_8") (pintype "passive"))
    )
    (net (code "159") (name "SEG24") (class "Default")
      (node (ref "LED24") (pin "8") (pinfunction "COM_8") (pintype "passive"))
      (node (ref "X4") (pin "7") (pinfunction "S_7") (pintype "passive"))
    )
    (net (code "160") (name "SEG25") (class "Default")
      (node (ref "LED25") (pin "8") (pinfunction "COM_8") (pintype "passive"))
      (node (ref "X4") (pin "6") (pinfunction "S_6") (pintype "passive"))
    )
    (net (code "161") (name "SEG26") (class "Default")
      (node (ref "LED26") (pin "8") (pinfunction "COM_8") (pintype "passive"))
      (node (ref "X4") (pin "5") (pinfunction "S_5") (pintype "passive"))
    )
    (net (code "162") (name "SEG27") (class "Default")
      (node (ref "LED27") (pin "8") (pinfunction "COM_8") (pintype "passive"))
      (node (ref "X4") (pin "4") (pinfunction "S_4") (pintype "passive"))
    )
    (net (code "163") (name "SEG28") (class "Default")
      (node (ref "LED28") (pin "8") (pinfunction "COM_8") (pintype "passive"))
      (node (ref "X4") (pin "3") (pinfunction "S_3") (pintype "passive"))
    )
    (net (code "164") (name "SEG29") (class "Default")
      (node (ref "LED29") (pin "8") (pinfunction "COM_8") (pintype "passive"))
      (node (ref "X4") (pin "2") (pinfunction "S_2") (pintype "passive"))
    )
    (net (code "165") (name "SEG30") (class "Default")
      (node (ref "LED30") (pin "8") (pinfunction "COM_8") (pintype "passive"))
      (node (ref "X4") (pin "1") (pinfunction "S_1") (pintype "passive"))
    )
    (net (code "166") (name "SEG31") (class "Default")
      (node (ref "LED31") (pin "8") (pinfunction "COM_8") (pintype "passive"))
      (node (ref "X5") (pin "10") (pinfunction "S_10") (pintype "passive"))
    )
    (net (code "167") (name "SEG32") (class "Default")
      (node (ref "LED32") (pin "8") (pinfunction "COM_8") (pintype "passive"))
      (node (ref "X5") (pin "9") (pinfunction "S_9") (pintype "passive"))
    )
    (net (code "168") (name "SEG33") (class "Default")
      (node (ref "LED33") (pin "8") (pinfunction "COM_8") (pintype "passive"))
      (node (ref "X5") (pin "8") (pinfunction "S_8") (pintype "passive"))
    )
    (net (code "169") (name "SEG34") (class "Default")
      (node (ref "LED34") (pin "8") (pinfunction "COM_8") (pintype "passive"))
      (node (ref "X5") (pin "7") (pinfunction "S_7") (pintype "passive"))
    )
    (net (code "170") (name "SEG35") (class "Default")
      (node (ref "LED35") (pin "8") (pinfunction "COM_8") (pintype "passive"))
      (node (ref "X5") (pin "6") (pinfunction "S_6") (pintype "passive"))
    )
    (net (code "171") (name "SEG36") (class "Default")
      (node (ref "LED36") (pin "8") (pinfunction "COM_8") (pintype "passive"))
      (node (ref "X5") (pin "5") (pinfunction "S_5") (pintype "passive"))
    )
    (net (code "172") (name "SEG37") (class "Default")
      (node (ref "LED37") (pin "8") (pinfunction "COM_8") (pintype "passive"))
      (node (ref "X5") (pin "4") (pinfunction "S_4") (pintype "passive"))
    )
    (net (code "173") (name "SEG38") (class "Default")
      (node (ref "LED38") (pin "8") (pinfunction "COM_8") (pintype "passive"))
      (node (ref "X5") (pin "3") (pinfunction "S_3") (pintype "passive"))
    )
    (net (code "174") (name "SEG39") (class "Default")
      (node (ref "LED39") (pin "8") (pinfunction "COM_8") (pintype "passive"))
      (node (ref "X5") (pin "2") (pinfunction "S_2") (pintype "passive"))
    )
    (net (code "175") (name "SEG40") (class "Default")
      (node (ref "LED40") (pin "8") (pinfunction "COM_8") (pintype "passive"))
      (node (ref "X5") (pin "1") (pinfunction "S_1") (pintype "passive"))
    )
    (net (code "176") (name "SH_CP") (class "Default")
      (node (ref "IC1") (pin "11") (pinfunction "SCK_11") (pintype "input"))
      (node (ref "IC2") (pin "11") (pinfunction "SCK_11") (pintype "input"))
      (node (ref "IC3") (pin "11") (pinfunction "SCK_11") (pintype "input"))
      (node (ref "IC4") (pin "11") (pinfunction "SCK_11") (pintype "input"))
      (node (ref "IC5") (pin "11") (pinfunction "SCK_11") (pintype "input"))
      (node (ref "X11") (pin "2") (pinfunction "S_2") (pintype "passive"))
    )
    (net (code "177") (name "ST_CP") (class "Default")
      (node (ref "IC1") (pin "12") (pinfunction "RCK_12") (pintype "input"))
      (node (ref "IC2") (pin "12") (pinfunction "RCK_12") (pintype "input"))
      (node (ref "IC3") (pin "12") (pinfunction "RCK_12") (pintype "input"))
      (node (ref "IC4") (pin "12") (pinfunction "RCK_12") (pintype "input"))
      (node (ref "IC5") (pin "12") (pinfunction "RCK_12") (pintype "input"))
      (node (ref "X11") (pin "1") (pinfunction "S_1") (pintype "passive"))
    )
    (net (code "178") (name "VCC") (class "Default")
      (node (ref "IC1") (pin "16") (pinfunction "VCC_16") (pintype "power_in"))
      (node (ref "IC10") (pin "10") (pinfunction "CD+_10") (pintype "passive"))
      (node (ref "IC2") (pin "16") (pinfunction "VCC_16") (pintype "power_in"))
      (node (ref "IC3") (pin "16") (pinfunction "VCC_16") (pintype "power_in"))
      (node (ref "IC4") (pin "16") (pinfunction "VCC_16") (pintype "power_in"))
      (node (ref "IC5") (pin "16") (pinfunction "VCC_16") (pintype "power_in"))
      (node (ref "IC6") (pin "10") (pinfunction "CD+_10") (pintype "passive"))
      (node (ref "IC7") (pin "10") (pinfunction "CD+_10") (pintype "passive"))
      (node (ref "IC8") (pin "10") (pinfunction "CD+_10") (pintype "passive"))
      (node (ref "IC9") (pin "10") (pinfunction "CD+_10") (pintype "passive"))
      (node (ref "T1") (pin "3") (pinfunction "C_3") (pintype "passive"))
      (node (ref "T2") (pin "3") (pinfunction "C_3") (pintype "passive"))
      (node (ref "T3") (pin "3") (pinfunction "C_3") (pintype "passive"))
      (node (ref "T4") (pin "3") (pinfunction "C_3") (pintype "passive"))
      (node (ref "T5") (pin "3") (pinfunction "C_3") (pintype "passive"))
      (node (ref "T6") (pin "3") (pinfunction "C_3") (pintype "passive"))
      (node (ref "T7") (pin "3") (pinfunction "C_3") (pintype "passive"))
      (node (ref "T8") (pin "3") (pinfunction "C_3") (pintype "passive"))
    )
    (net (code "179") (name "unconnected-(IC5A-QH*-Pad9)") (class "Default")
      (node (ref "IC5") (pin "9") (pinfunction "QH*_9") (pintype "tri_state"))
    )
    (net (code "180") (name "unconnected-(LED1-COM-Pad3)") (class "Default")
      (node (ref "LED1") (pin "3") (pinfunction "COM_3") (pintype "passive"))
    )
    (net (code "181") (name "unconnected-(LED2-COM-Pad3)") (class "Default")
      (node (ref "LED2") (pin "3") (pinfunction "COM_3") (pintype "passive"))
    )
    (net (code "182") (name "unconnected-(LED3-COM-Pad3)") (class "Default")
      (node (ref "LED3") (pin "3") (pinfunction "COM_3") (pintype "passive"))
    )
    (net (code "183") (name "unconnected-(LED4-COM-Pad3)") (class "Default")
      (node (ref "LED4") (pin "3") (pinfunction "COM_3") (pintype "passive"))
    )
    (net (code "184") (name "unconnected-(LED5-COM-Pad3)") (class "Default")
      (node (ref "LED5") (pin "3") (pinfunction "COM_3") (pintype "passive"))
    )
    (net (code "185") (name "unconnected-(LED6-COM-Pad3)") (class "Default")
      (node (ref "LED6") (pin "3") (pinfunction "COM_3") (pintype "passive"))
    )
    (net (code "186") (name "unconnected-(LED7-COM-Pad3)") (class "Default")
      (node (ref "LED7") (pin "3") (pinfunction "COM_3") (pintype "passive"))
    )
    (net (code "187") (name "unconnected-(LED8-COM-Pad3)") (class "Default")
      (node (ref "LED8") (pin "3") (pinfunction "COM_3") (pintype "passive"))
    )
    (net (code "188") (name "unconnected-(LED9-COM-Pad3)") (class "Default")
      (node (ref "LED9") (pin "3") (pinfunction "COM_3") (pintype "passive"))
    )
    (net (code "189") (name "unconnected-(LED10-COM-Pad3)") (class "Default")
      (node (ref "LED10") (pin "3") (pinfunction "COM_3") (pintype "passive"))
    )
    (net (code "190") (name "unconnected-(LED11-COM-Pad3)") (class "Default")
      (node (ref "LED11") (pin "3") (pinfunction "COM_3") (pintype "passive"))
    )
    (net (code "191") (name "unconnected-(LED12-COM-Pad3)") (class "Default")
      (node (ref "LED12") (pin "3") (pinfunction "COM_3") (pintype "passive"))
    )
    (net (code "192") (name "unconnected-(LED13-COM-Pad3)") (class "Default")
      (node (ref "LED13") (pin "3") (pinfunction "COM_3") (pintype "passive"))
    )
    (net (code "193") (name "unconnected-(LED14-COM-Pad3)") (class "Default")
      (node (ref "LED14") (pin "3") (pinfunction "COM_3") (pintype "passive"))
    )
    (net (code "194") (name "unconnected-(LED15-COM-Pad3)") (class "Default")
      (node (ref "LED15") (pin "3") (pinfunction "COM_3") (pintype "passive"))
    )
    (net (code "195") (name "unconnected-(LED16-COM-Pad3)") (class "Default")
      (node (ref "LED16") (pin "3") (pinfunction "COM_3") (pintype "passive"))
    )
    (net (code "196") (name "unconnected-(LED17-COM-Pad3)") (class "Default")
      (node (ref "LED17") (pin "3") (pinfunction "COM_3") (pintype "passive"))
    )
    (net (code "197") (name "unconnected-(LED18-COM-Pad3)") (class "Default")
      (node (ref "LED18") (pin "3") (pinfunction "COM_3") (pintype "passive"))
    )
    (net (code "198") (name "unconnected-(LED19-COM-Pad3)") (class "Default")
      (node (ref "LED19") (pin "3") (pinfunction "COM_3") (pintype "passive"))
    )
    (net (code "199") (name "unconnected-(LED20-COM-Pad3)") (class "Default")
      (node (ref "LED20") (pin "3") (pinfunction "COM_3") (pintype "passive"))
    )
    (net (code "200") (name "unconnected-(LED21-COM-Pad3)") (class "Default")
      (node (ref "LED21") (pin "3") (pinfunction "COM_3") (pintype "passive"))
    )
    (net (code "201") (name "unconnected-(LED22-COM-Pad3)") (class "Default")
      (node (ref "LED22") (pin "3") (pinfunction "COM_3") (pintype "passive"))
    )
    (net (code "202") (name "unconnected-(LED23-COM-Pad3)") (class "Default")
      (node (ref "LED23") (pin "3") (pinfunction "COM_3") (pintype "passive"))
    )
    (net (code "203") (name "unconnected-(LED24-COM-Pad3)") (class "Default")
      (node (ref "LED24") (pin "3") (pinfunction "COM_3") (pintype "passive"))
    )
    (net (code "204") (name "unconnected-(LED25-COM-Pad3)") (class "Default")
      (node (ref "LED25") (pin "3") (pinfunction "COM_3") (pintype "passive"))
    )
    (net (code "205") (name "unconnected-(LED26-COM-Pad3)") (class "Default")
      (node (ref "LED26") (pin "3") (pinfunction "COM_3") (pintype "passive"))
    )
    (net (code "206") (name "unconnected-(LED27-COM-Pad3)") (class "Default")
      (node (ref "LED27") (pin "3") (pinfunction "COM_3") (pintype "passive"))
    )
    (net (code "207") (name "unconnected-(LED28-COM-Pad3)") (class "Default")
      (node (ref "LED28") (pin "3") (pinfunction "COM_3") (pintype "passive"))
    )
    (net (code "208") (name "unconnected-(LED29-COM-Pad3)") (class "Default")
      (node (ref "LED29") (pin "3") (pinfunction "COM_3") (pintype "passive"))
    )
    (net (code "209") (name "unconnected-(LED30-COM-Pad3)") (class "Default")
      (node (ref "LED30") (pin "3") (pinfunction "COM_3") (pintype "passive"))
    )
    (net (code "210") (name "unconnected-(LED31-COM-Pad3)") (class "Default")
      (node (ref "LED31") (pin "3") (pinfunction "COM_3") (pintype "passive"))
    )
    (net (code "211") (name "unconnected-(LED32-COM-Pad3)") (class "Default")
      (node (ref "LED32") (pin "3") (pinfunction "COM_3") (pintype "passive"))
    )
    (net (code "212") (name "unconnected-(LED33-COM-Pad3)") (class "Default")
      (node (ref "LED33") (pin "3") (pinfunction "COM_3") (pintype "passive"))
    )
    (net (code "213") (name "unconnected-(LED34-COM-Pad3)") (class "Default")
      (node (ref "LED34") (pin "3") (pinfunction "COM_3") (pintype "passive"))
    )
    (net (code "214") (name "unconnected-(LED35-COM-Pad3)") (class "Default")
      (node (ref "LED35") (pin "3") (pinfunction "COM_3") (pintype "passive"))
    )
    (net (code "215") (name "unconnected-(LED36-COM-Pad3)") (class "Default")
      (node (ref "LED36") (pin "3") (pinfunction "COM_3") (pintype "passive"))
    )
    (net (code "216") (name "unconnected-(LED37-COM-Pad3)") (class "Default")
      (node (ref "LED37") (pin "3") (pinfunction "COM_3") (pintype "passive"))
    )
    (net (code "217") (name "unconnected-(LED38-COM-Pad3)") (class "Default")
      (node (ref "LED38") (pin "3") (pinfunction "COM_3") (pintype "passive"))
    )
    (net (code "218") (name "unconnected-(LED39-COM-Pad3)") (class "Default")
      (node (ref "LED39") (pin "3") (pinfunction "COM_3") (pintype "passive"))
    )
    (net (code "219") (name "unconnected-(LED40-COM-Pad3)") (class "Default")
      (node (ref "LED40") (pin "3") (pinfunction "COM_3") (pintype "passive"))
    )
  )
)
